# module_flags_calc.net
KiCad netlist of a schematic drawn in EAGLE
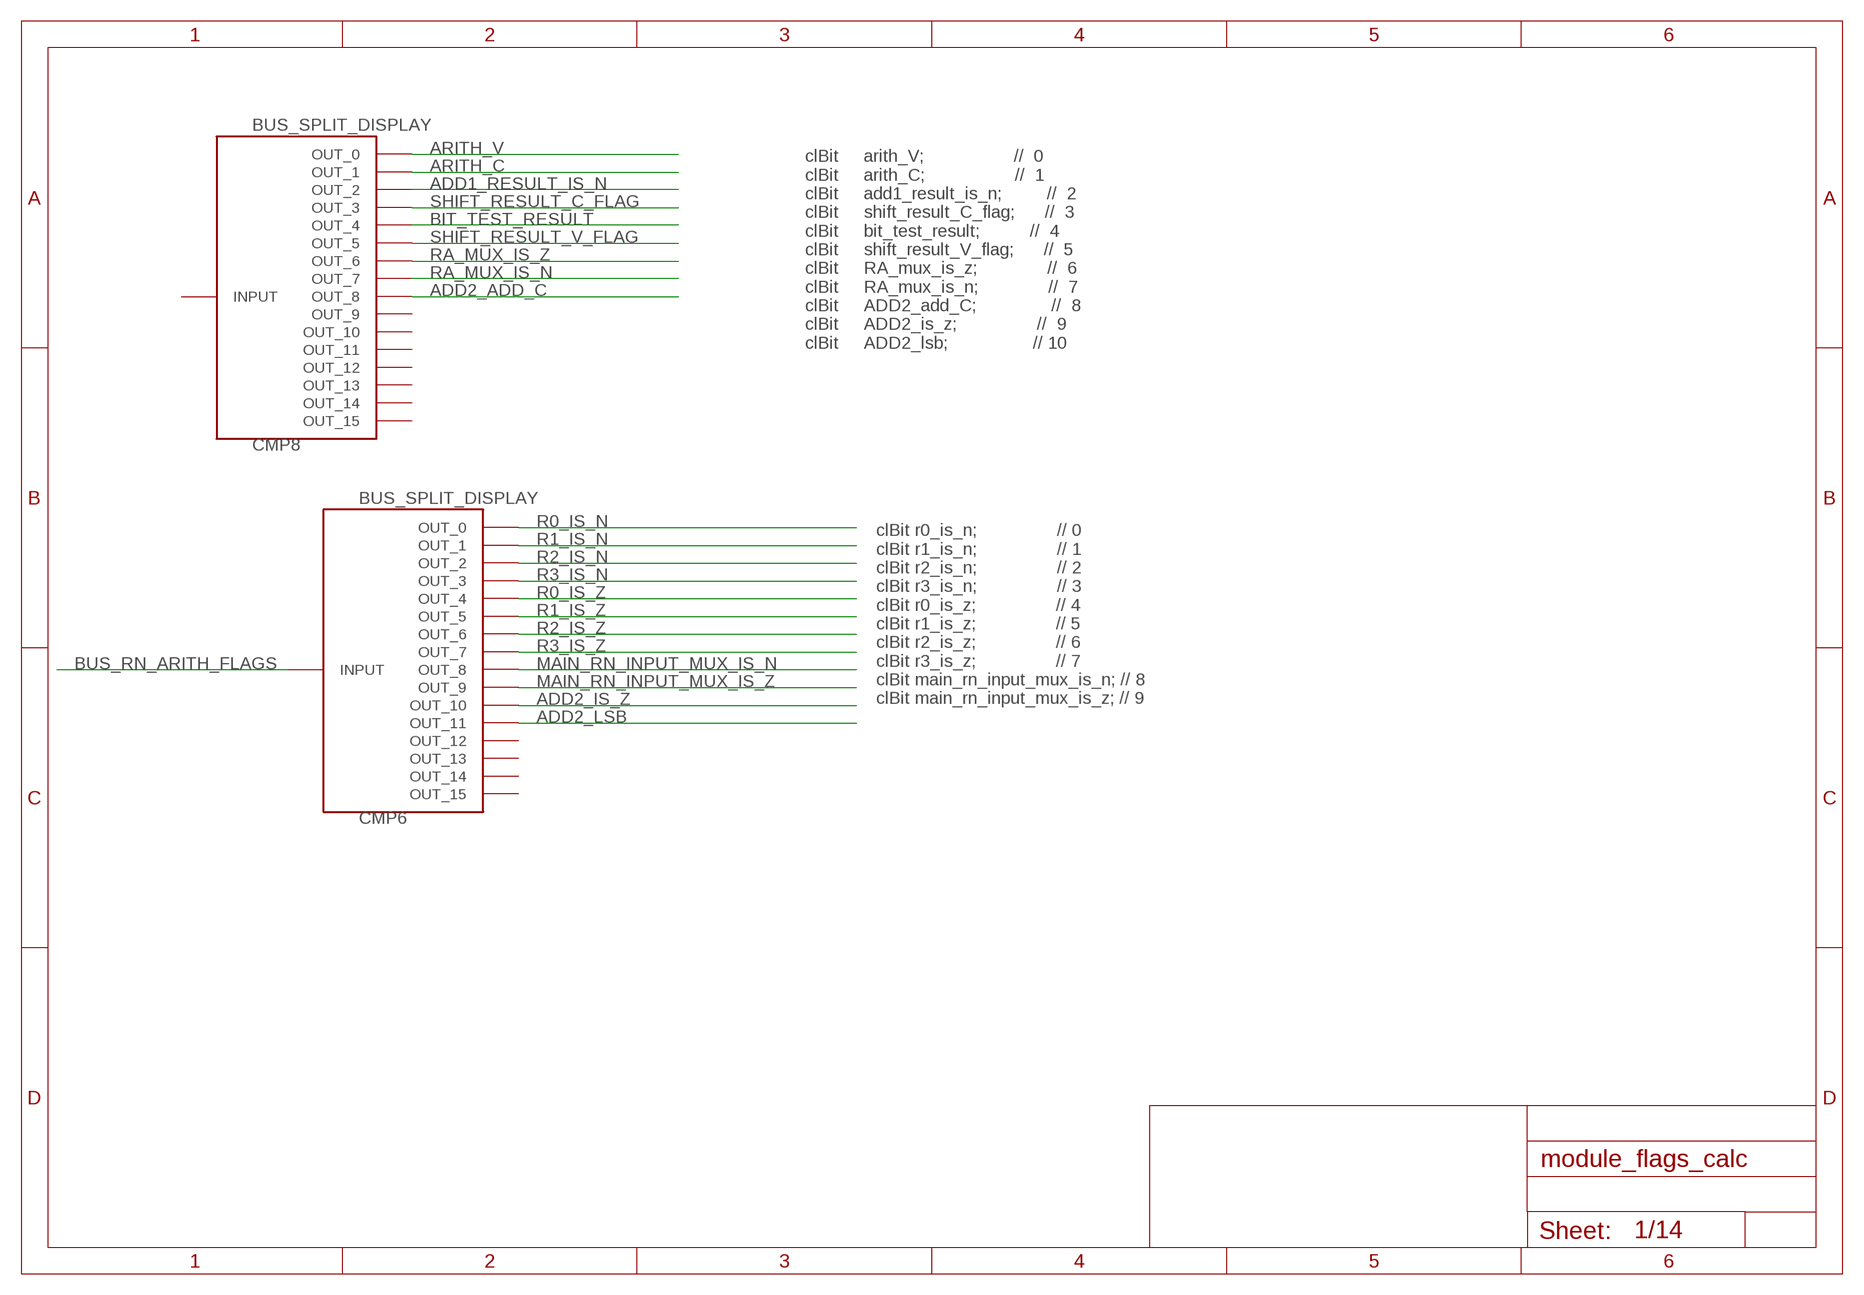
[diagram p0: schematic, sheet 1]
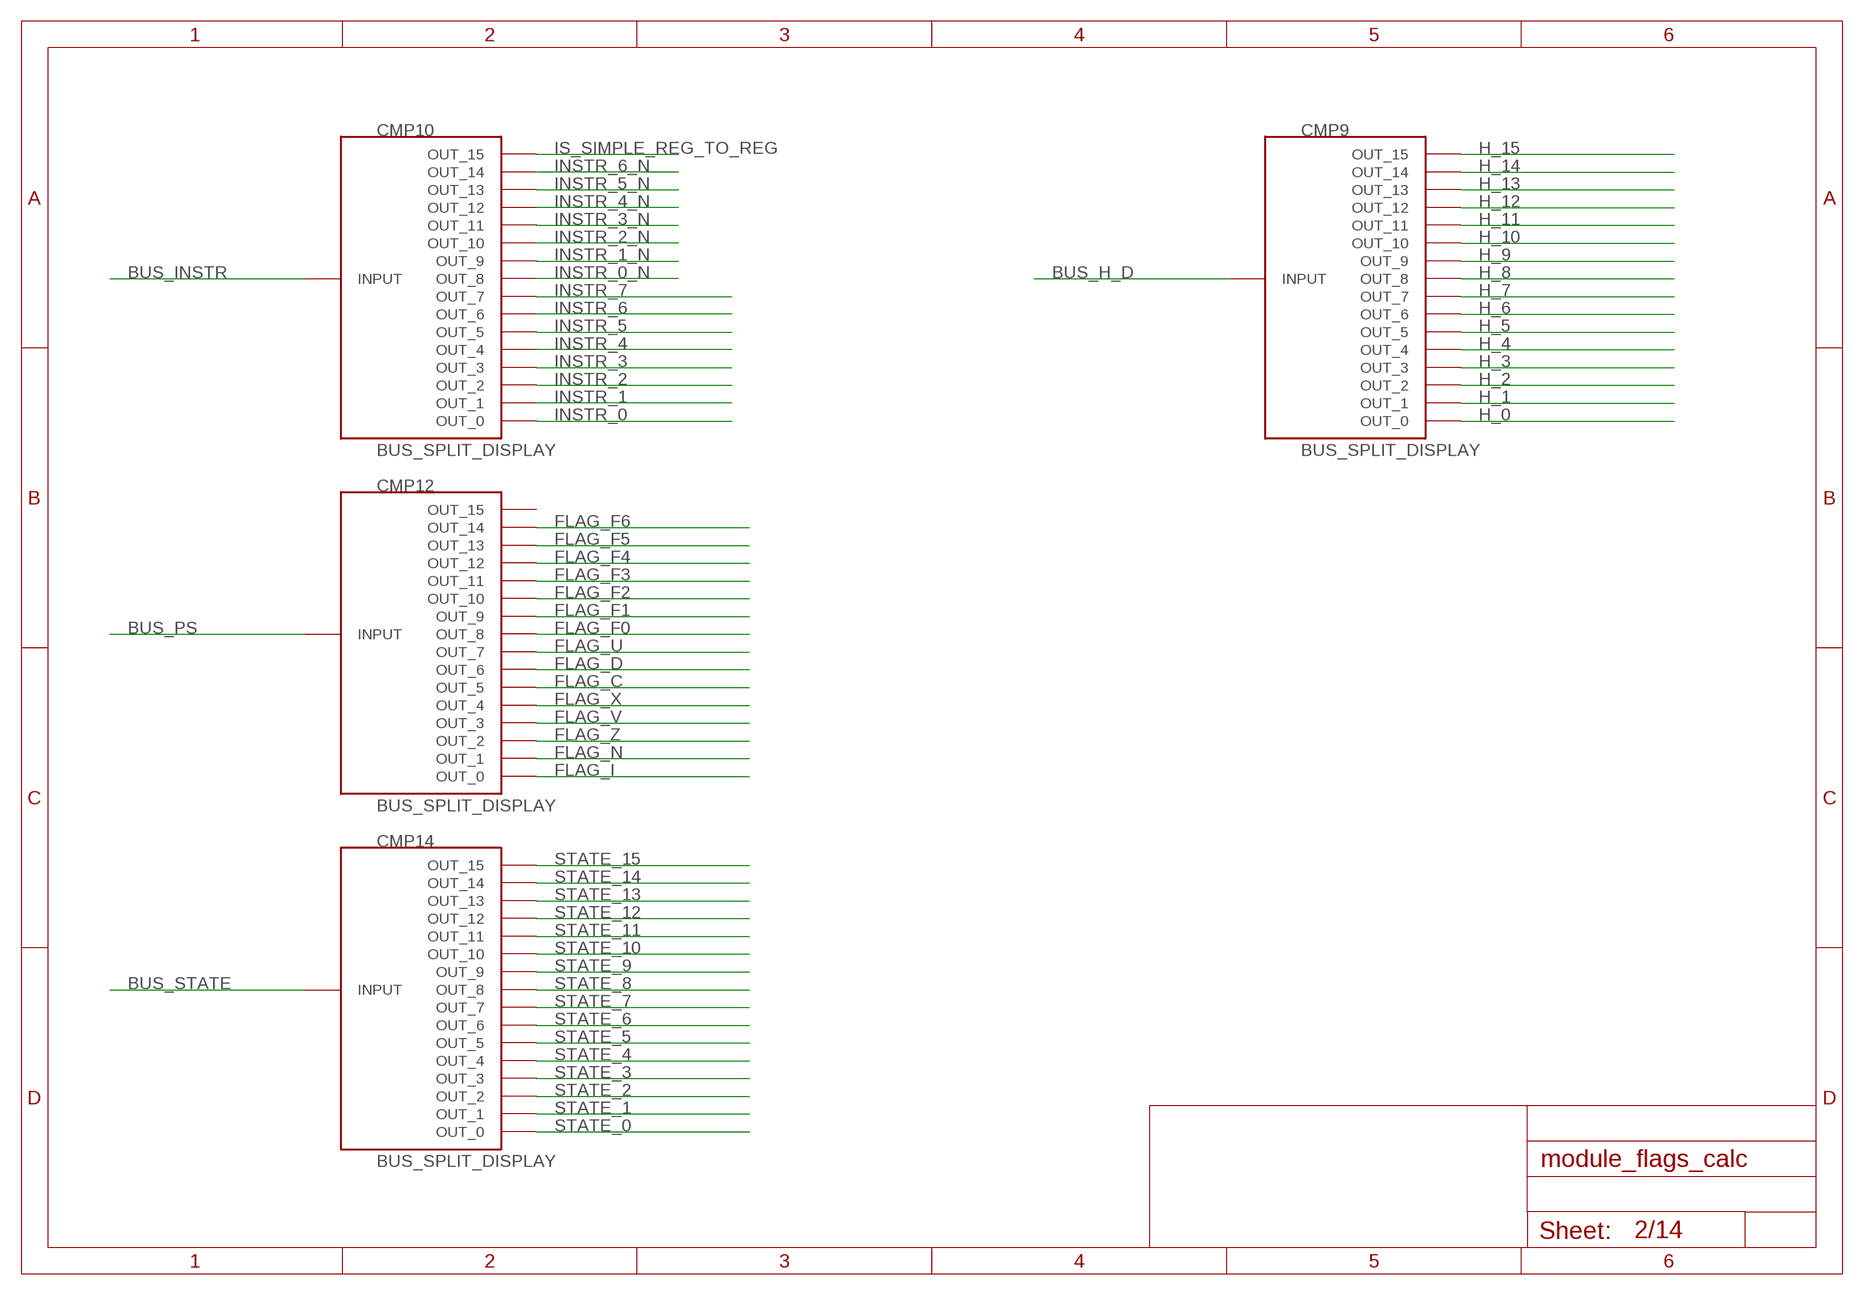
[diagram p1: schematic, sheet 2]
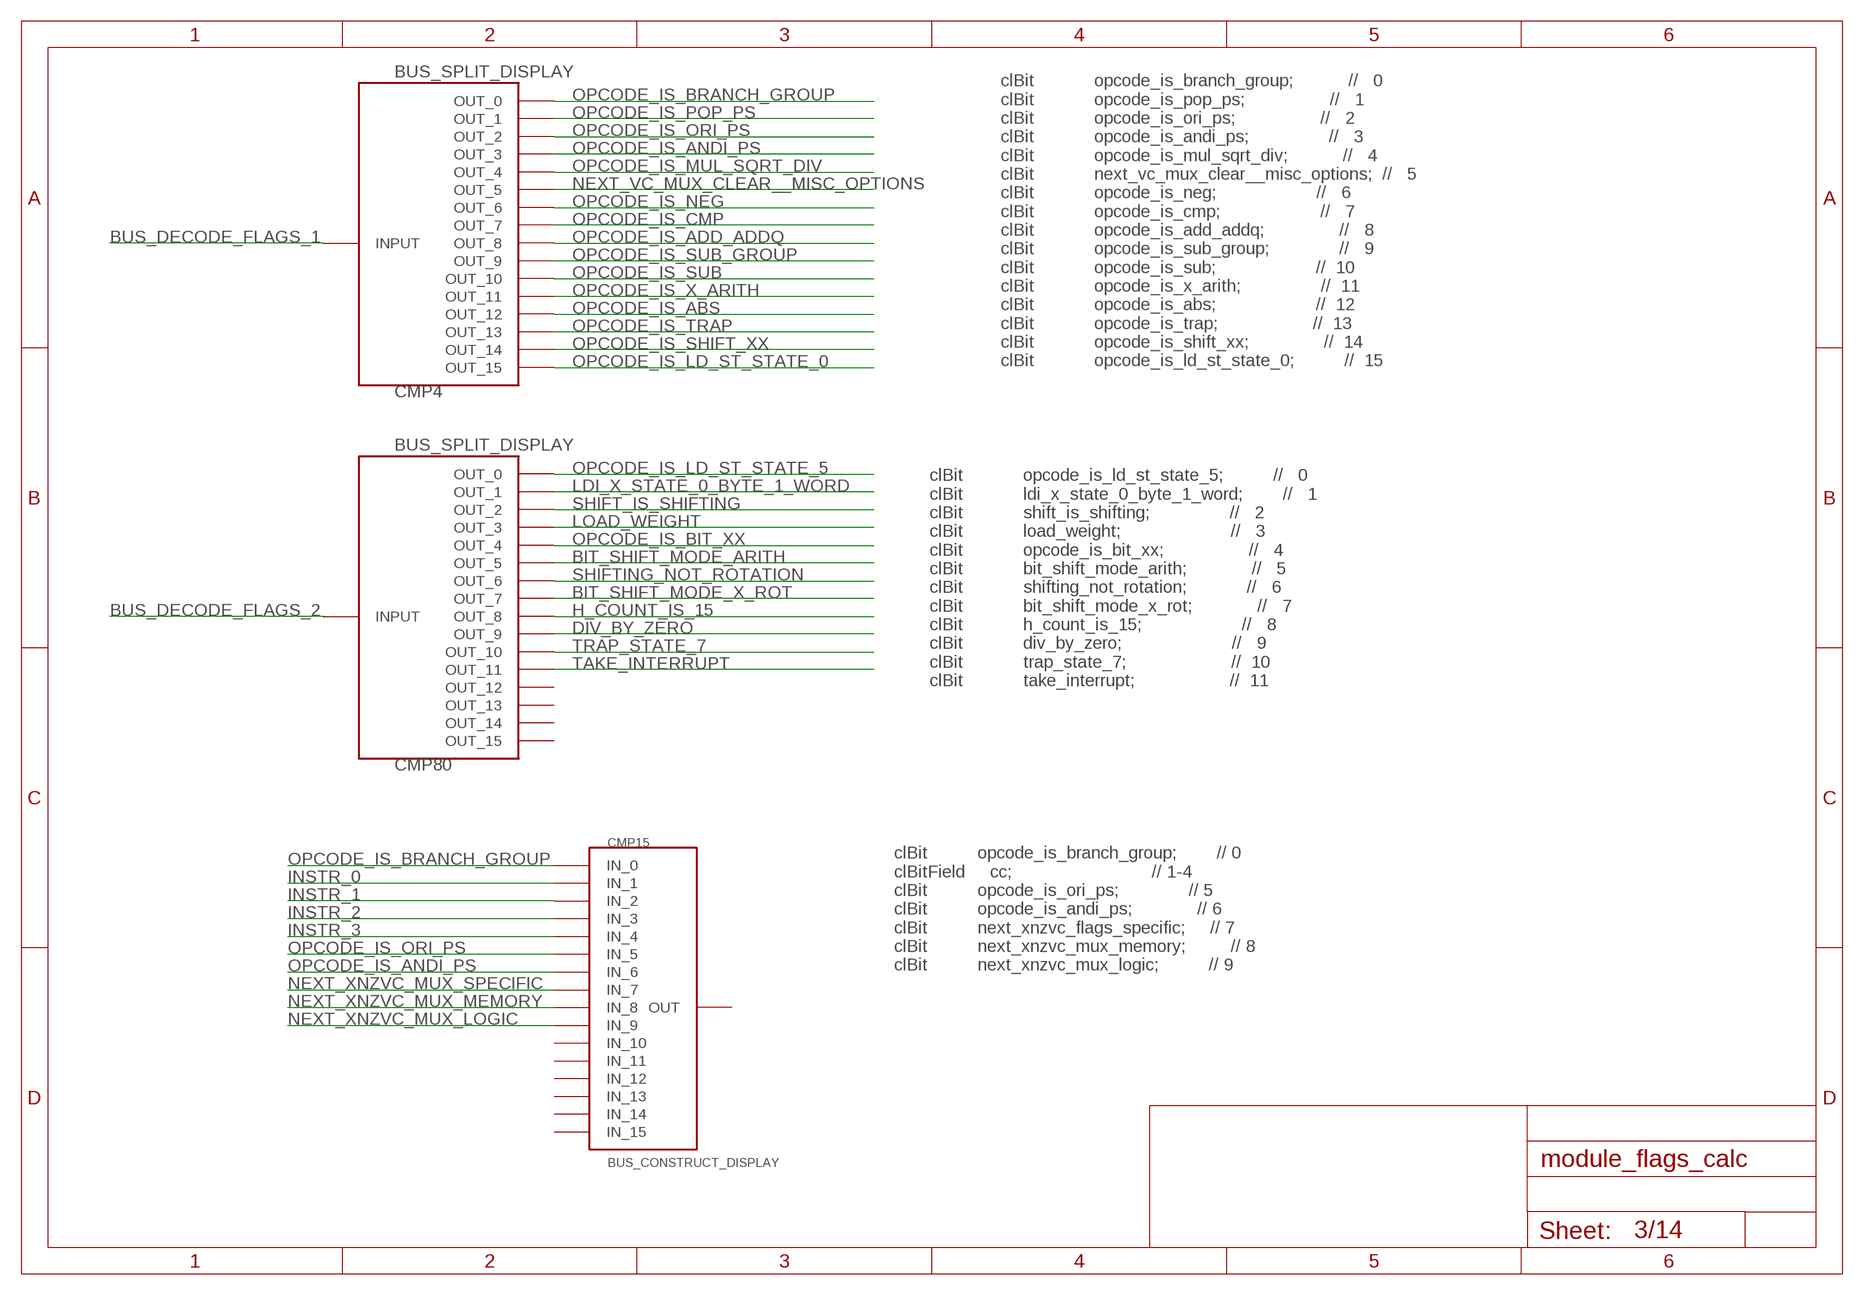
[diagram p2: schematic, sheet 3]
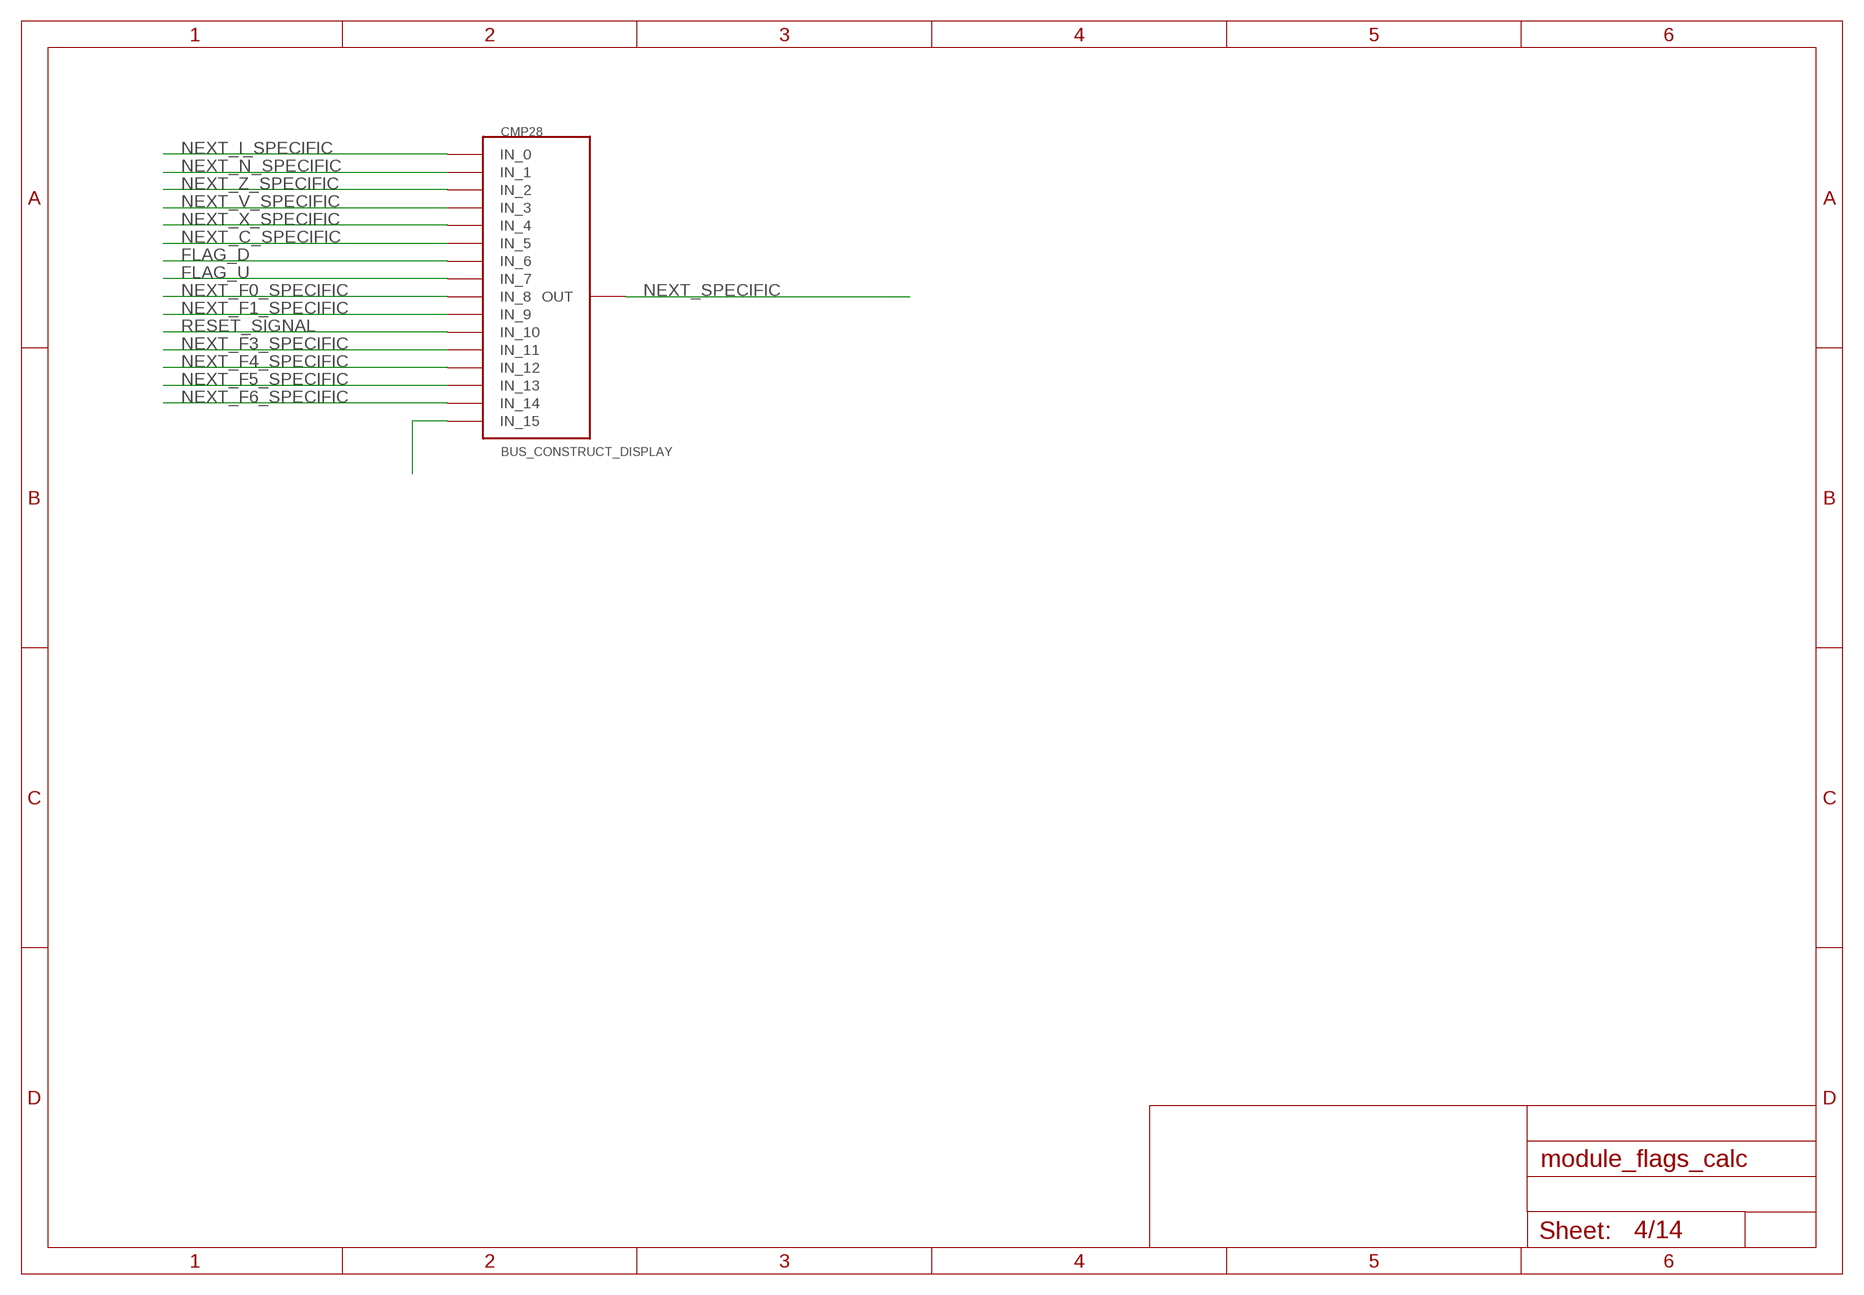
[diagram p3: schematic, sheet 4]
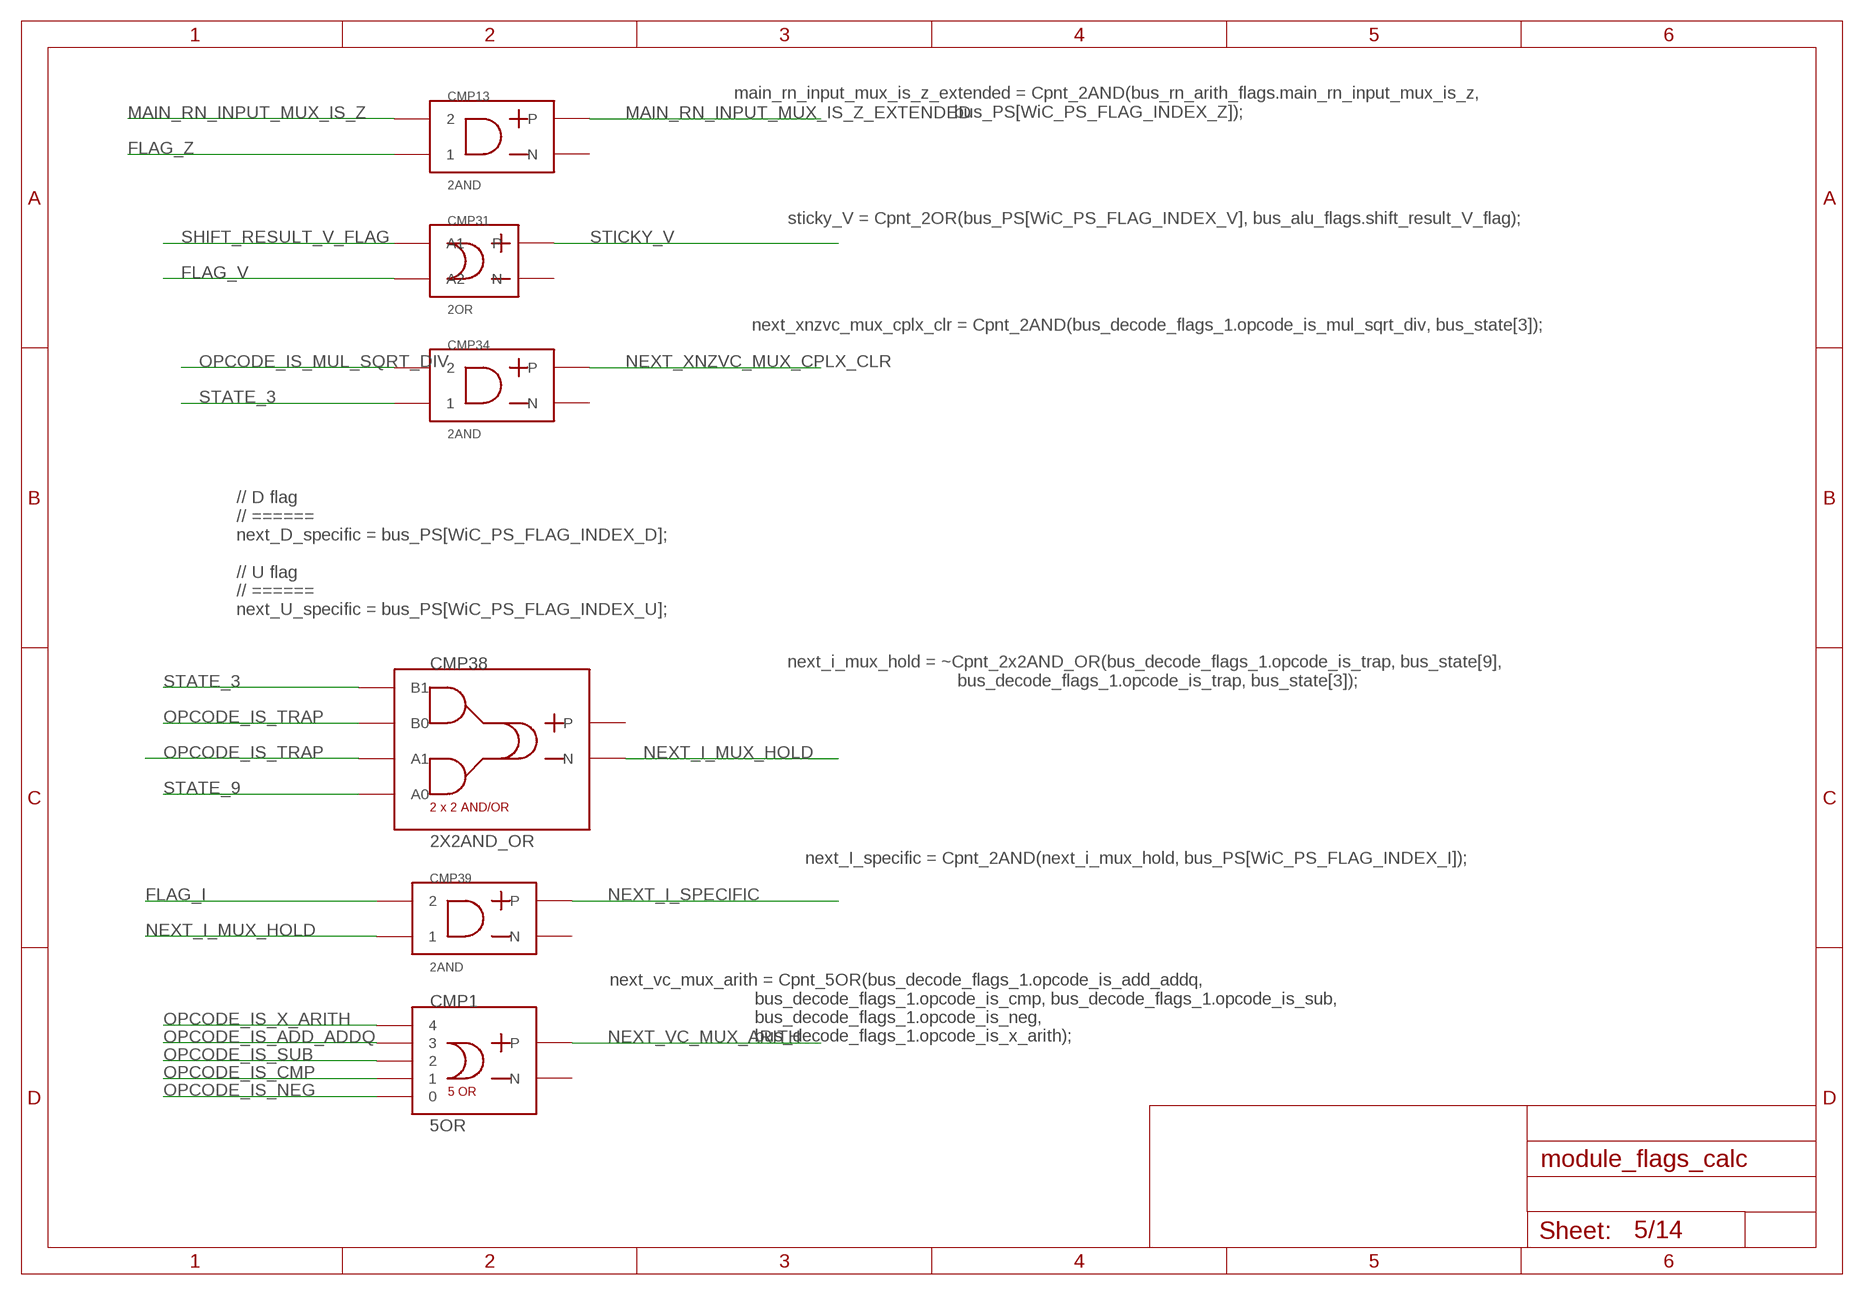
[diagram p4: schematic, sheet 5]
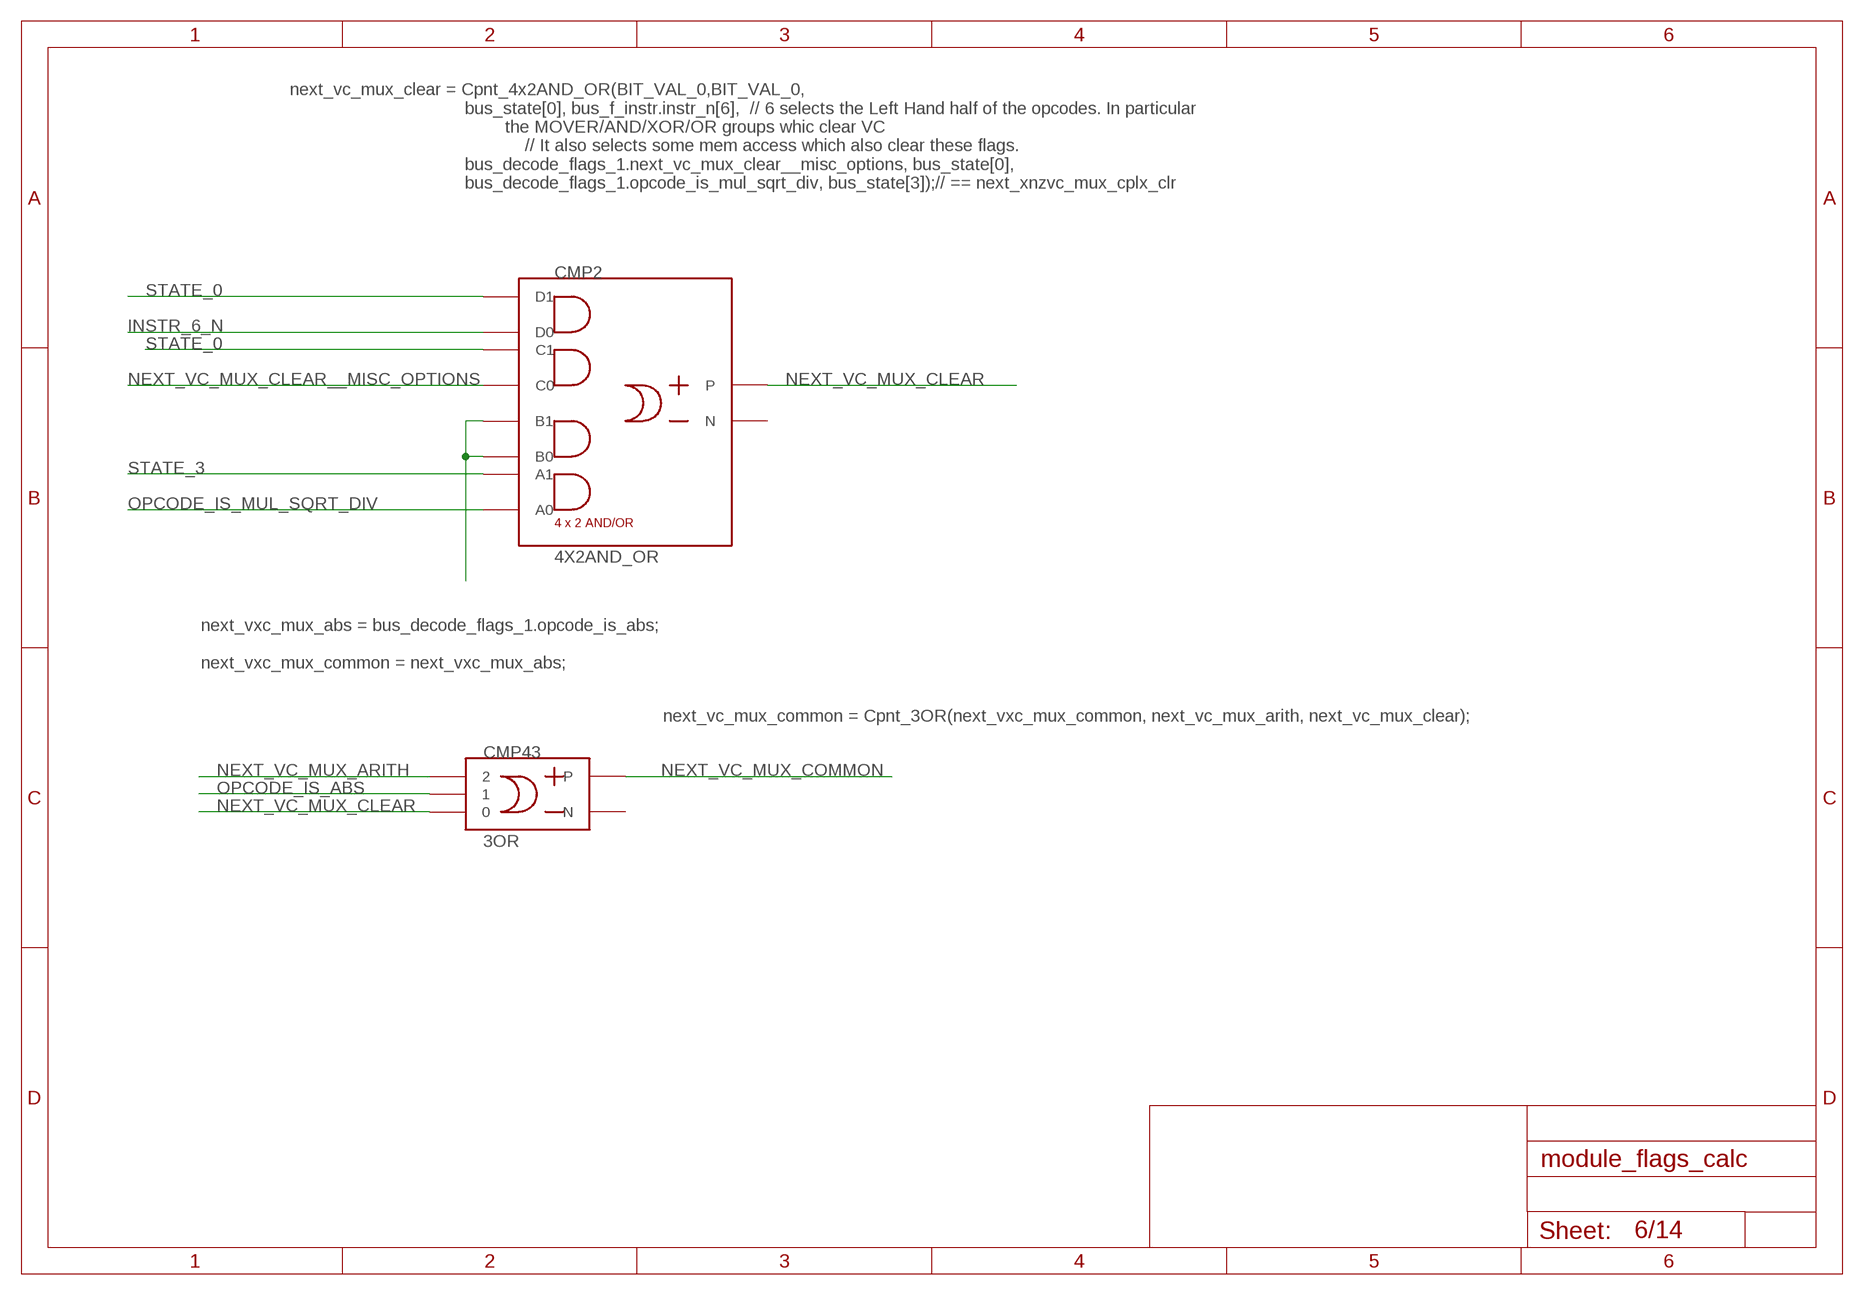
[diagram p5: schematic, sheet 6]
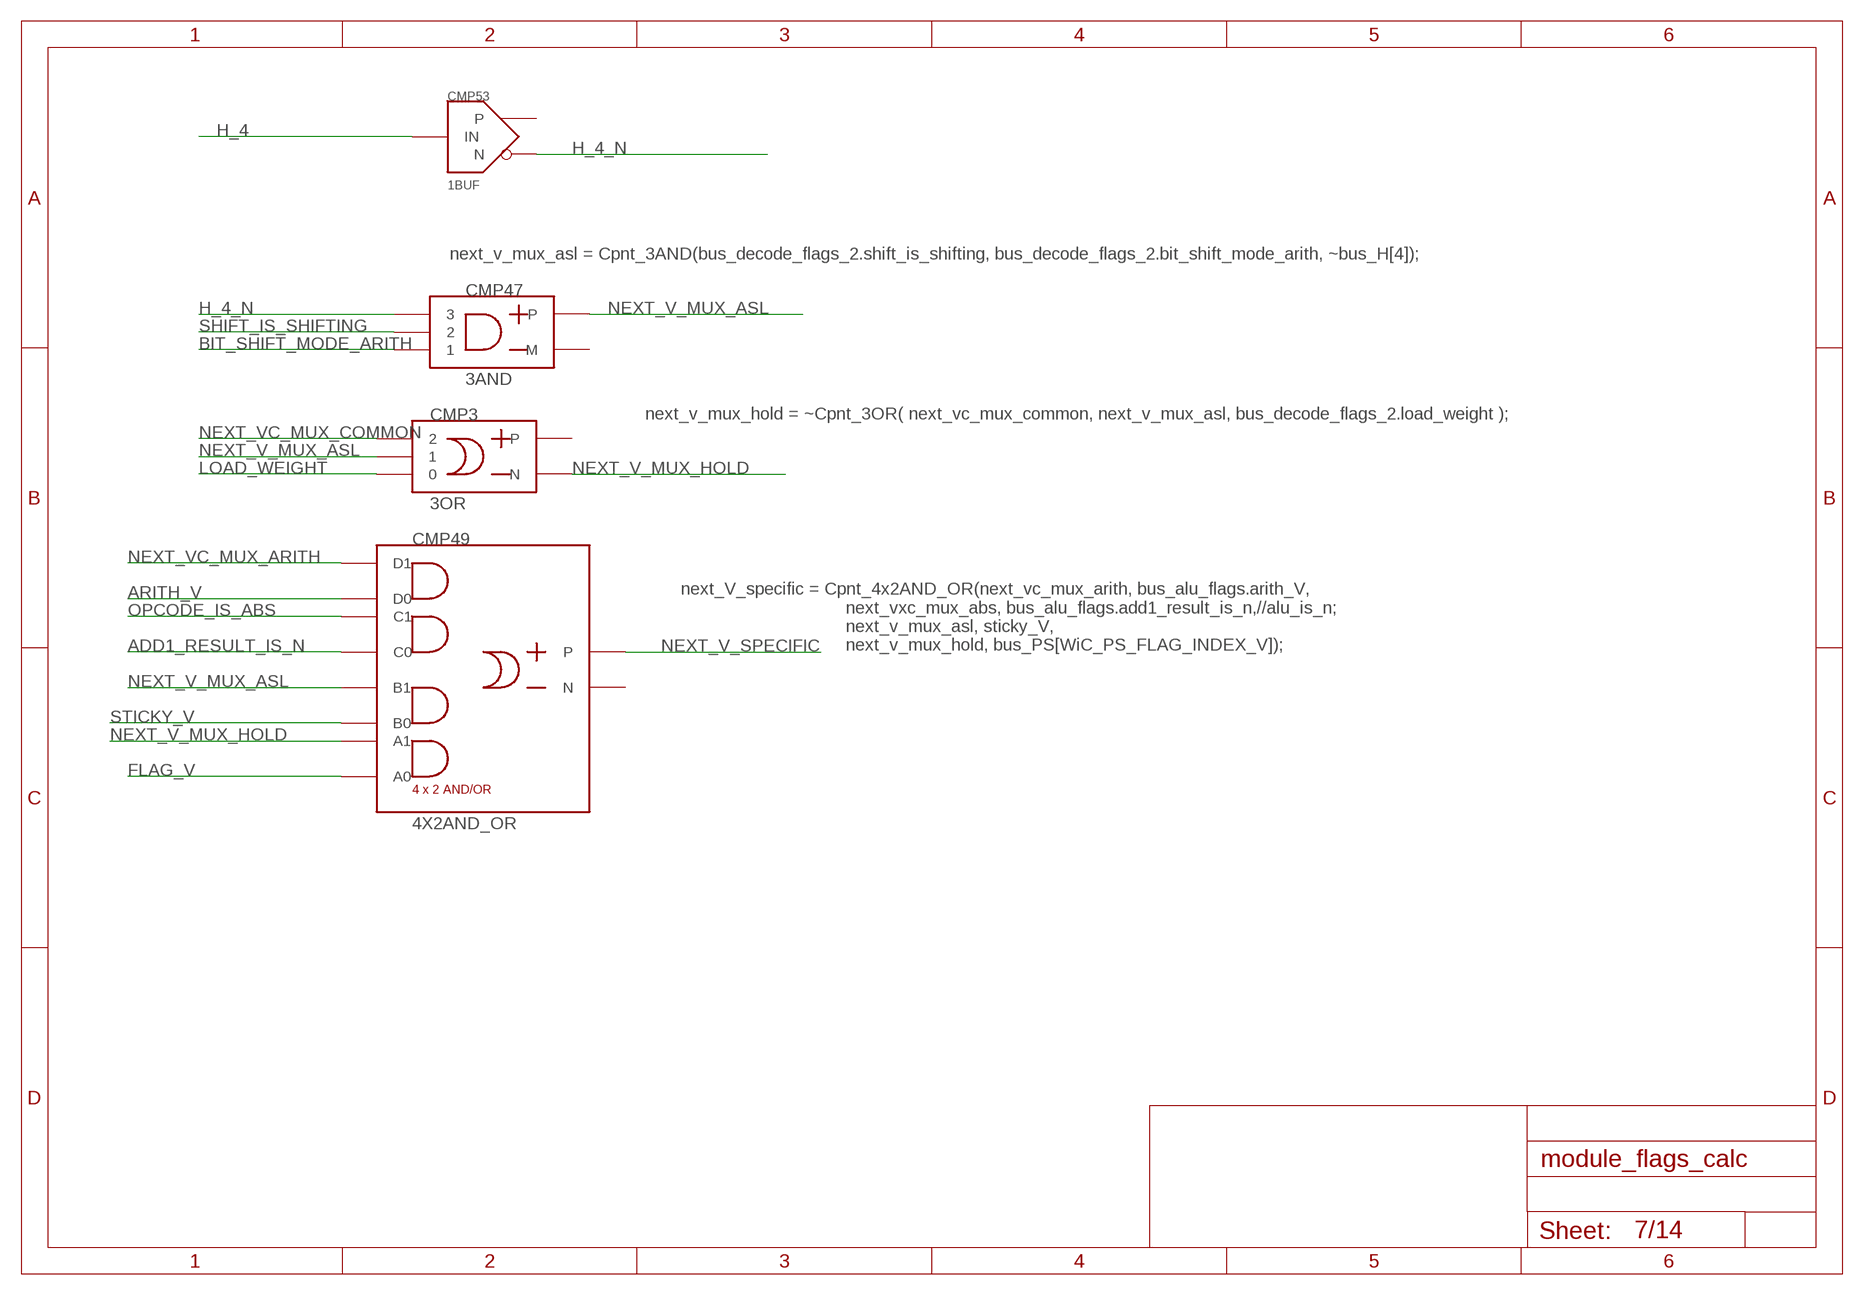
[diagram p6: schematic, sheet 7]
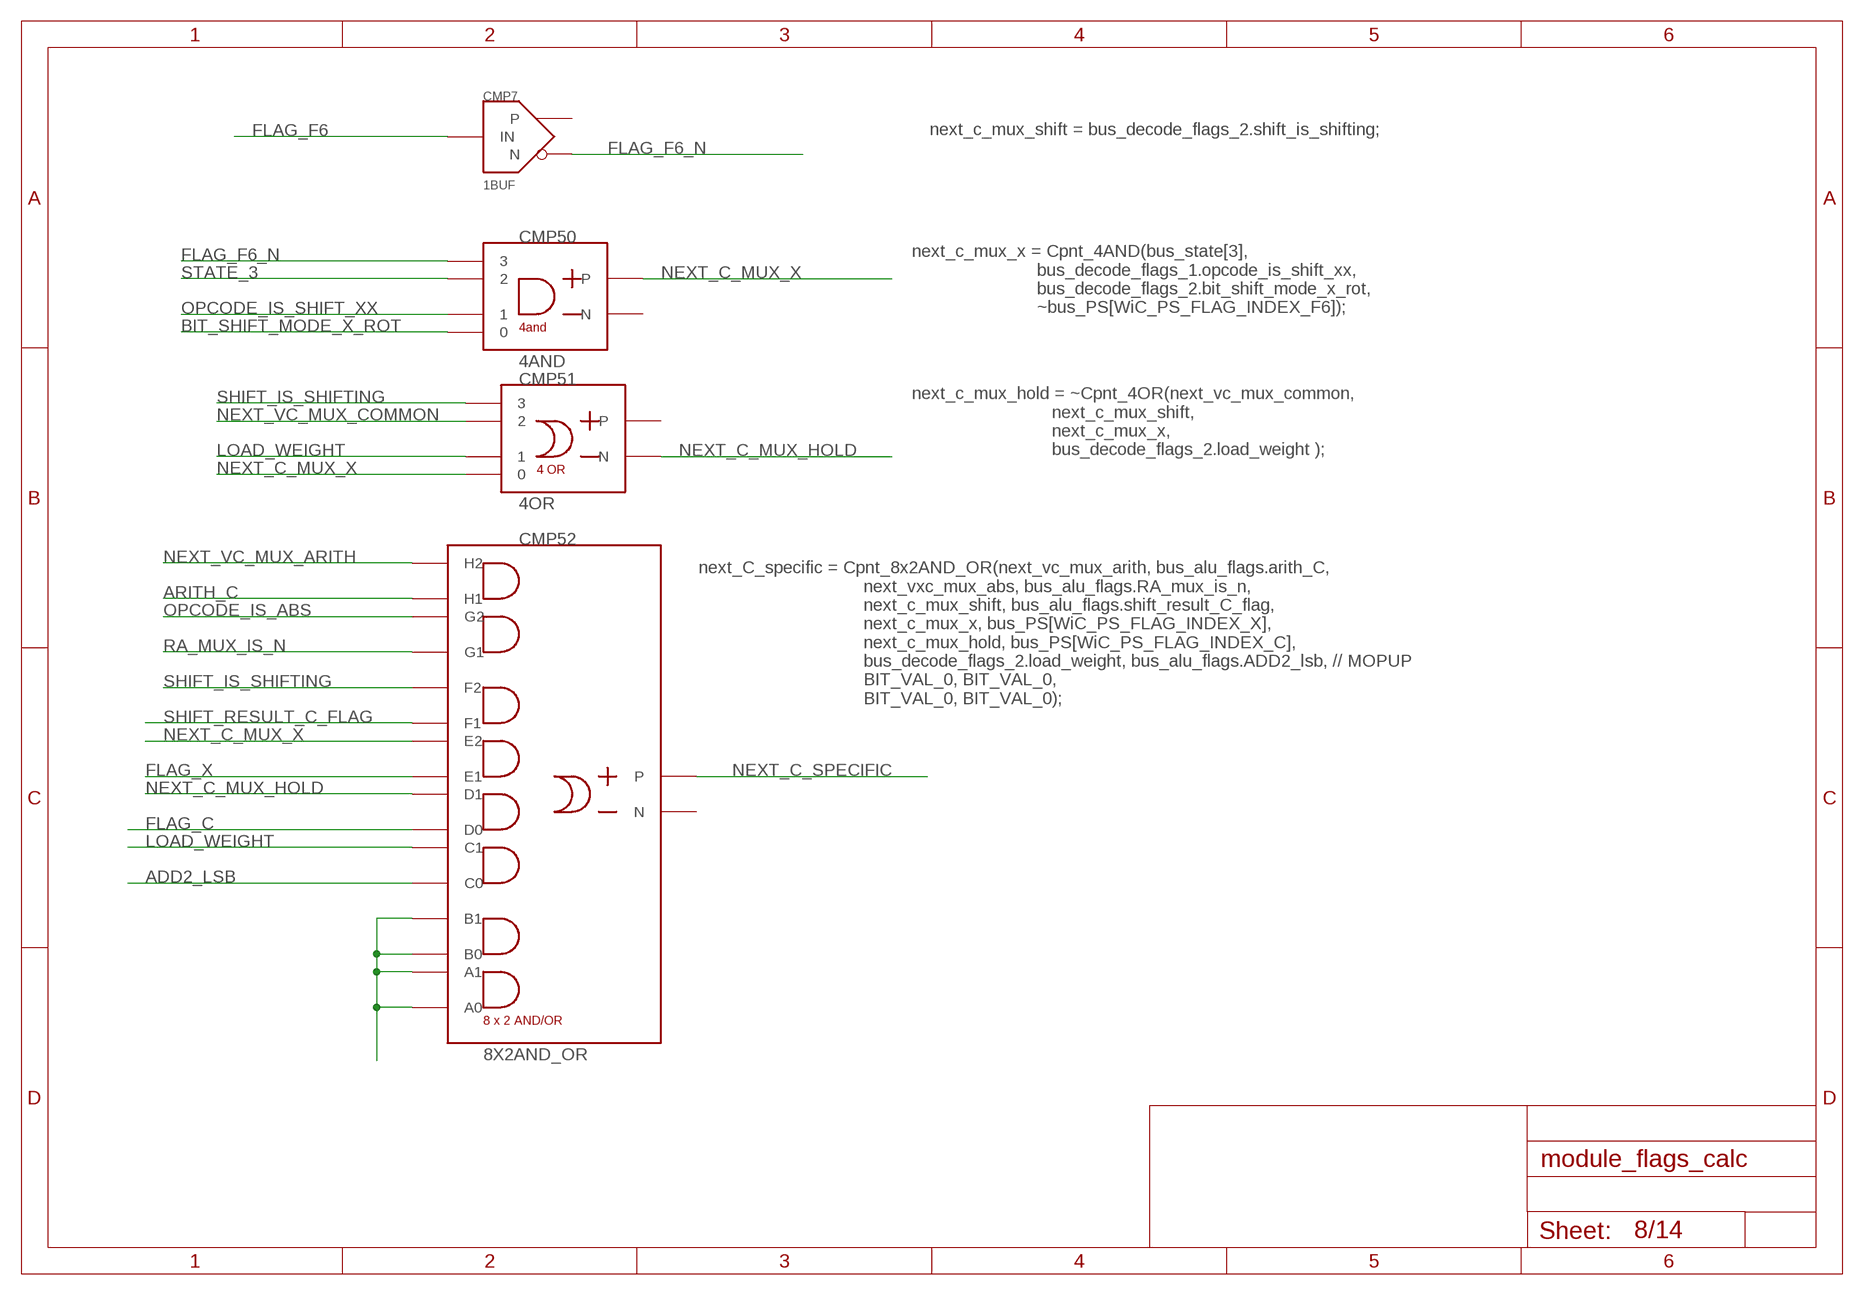
[diagram p7: schematic, sheet 8]
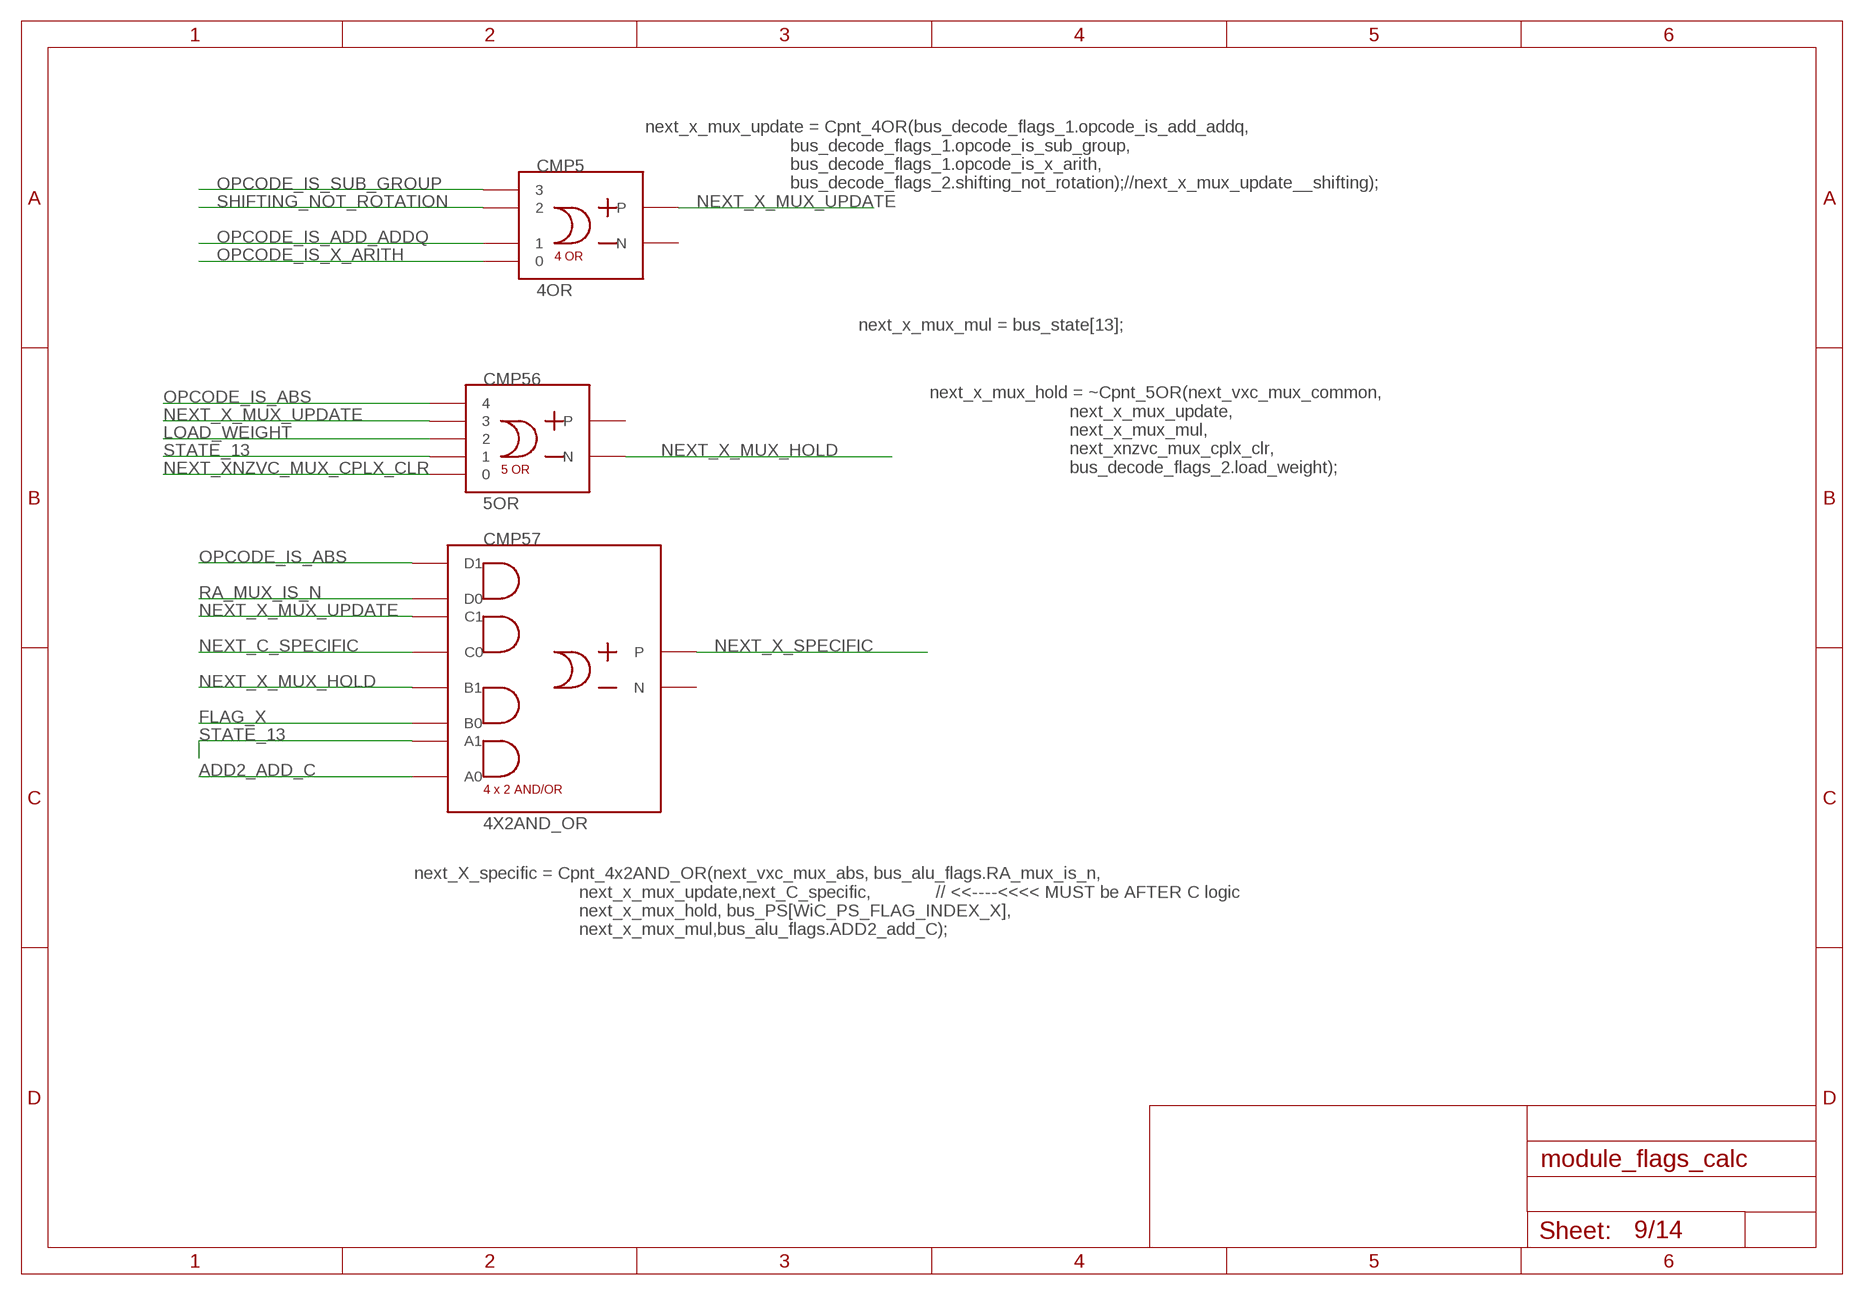
[diagram p8: schematic, sheet 9]
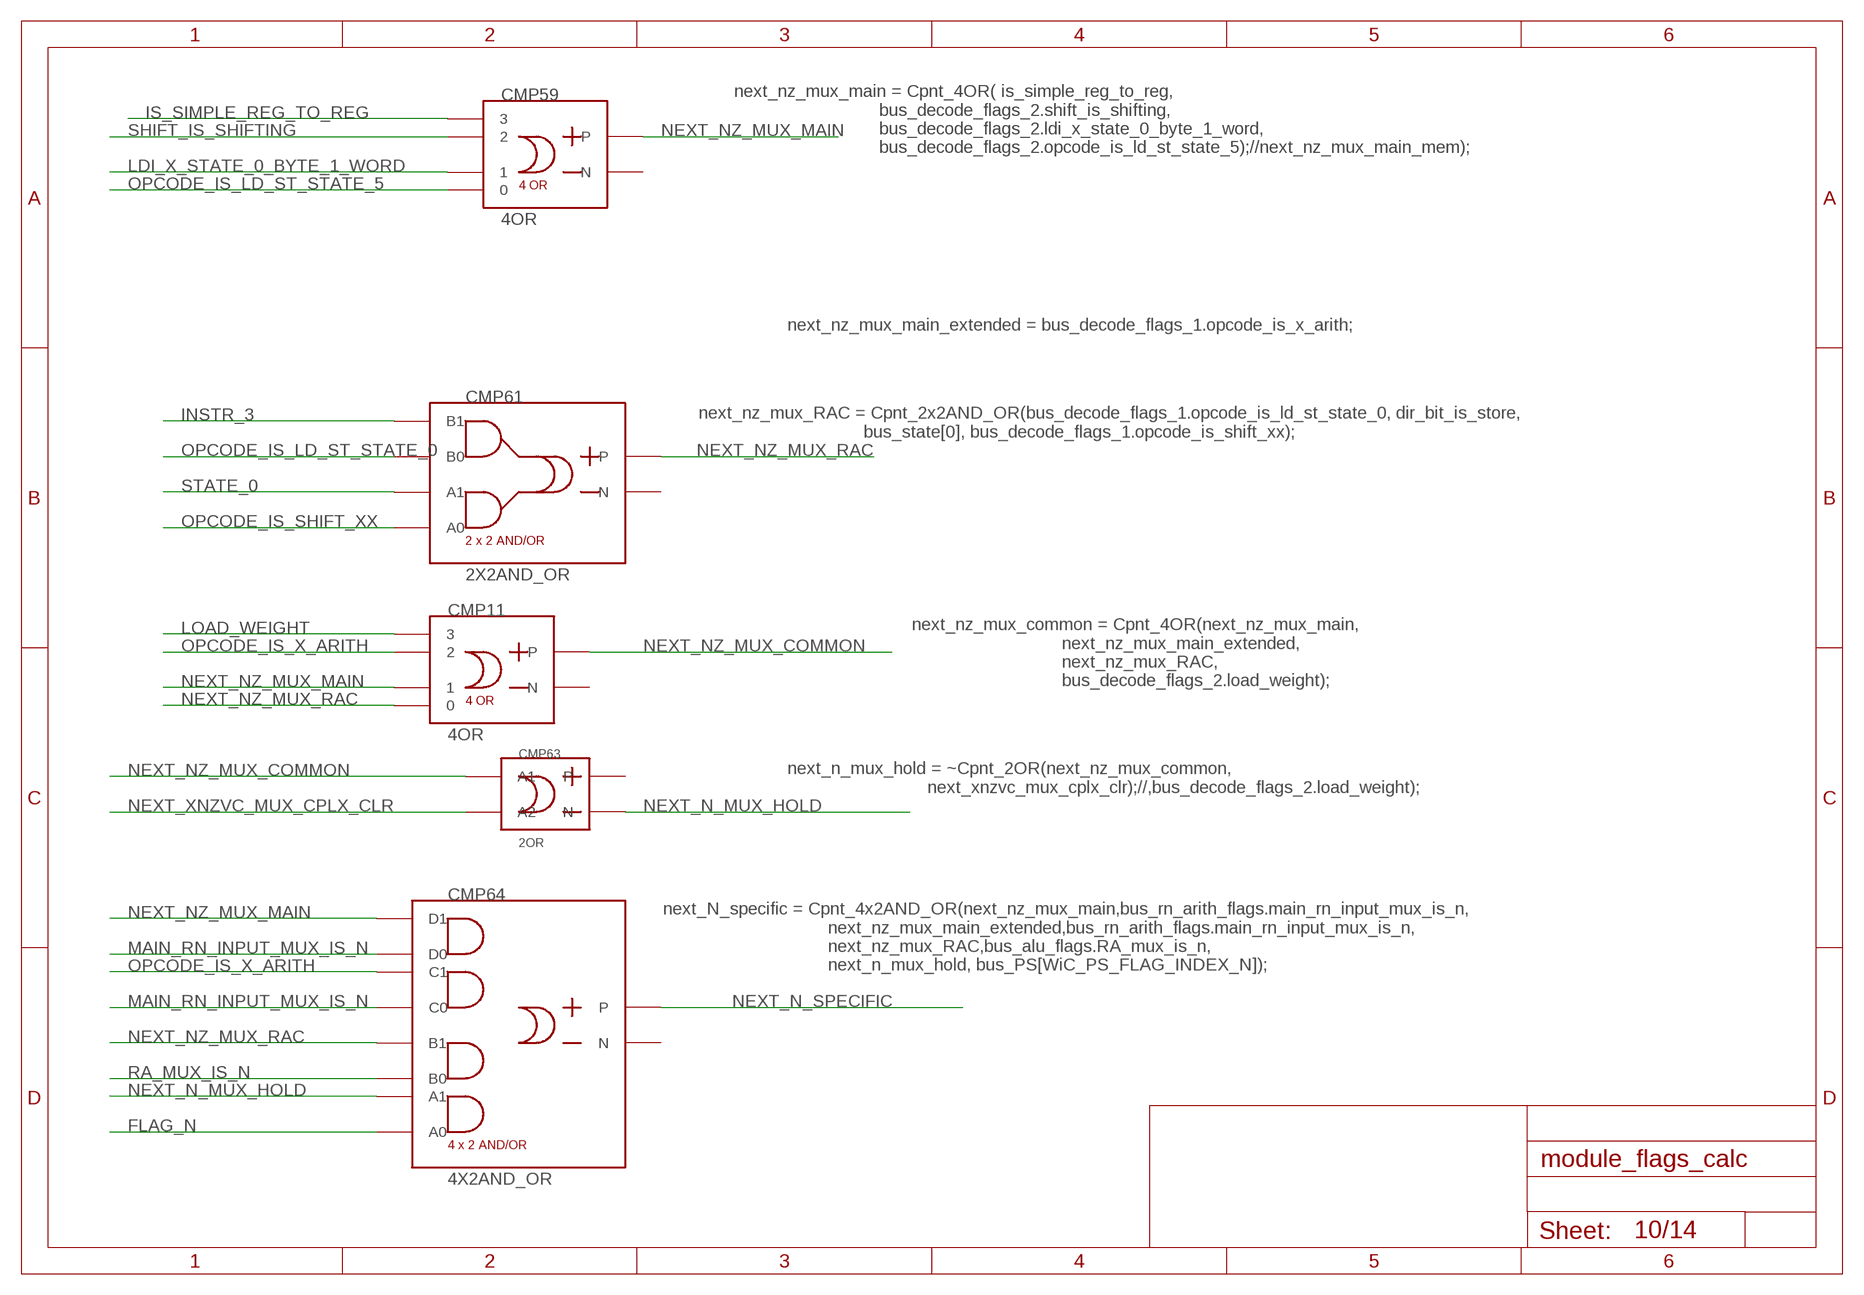
[diagram p9: schematic, sheet 10]
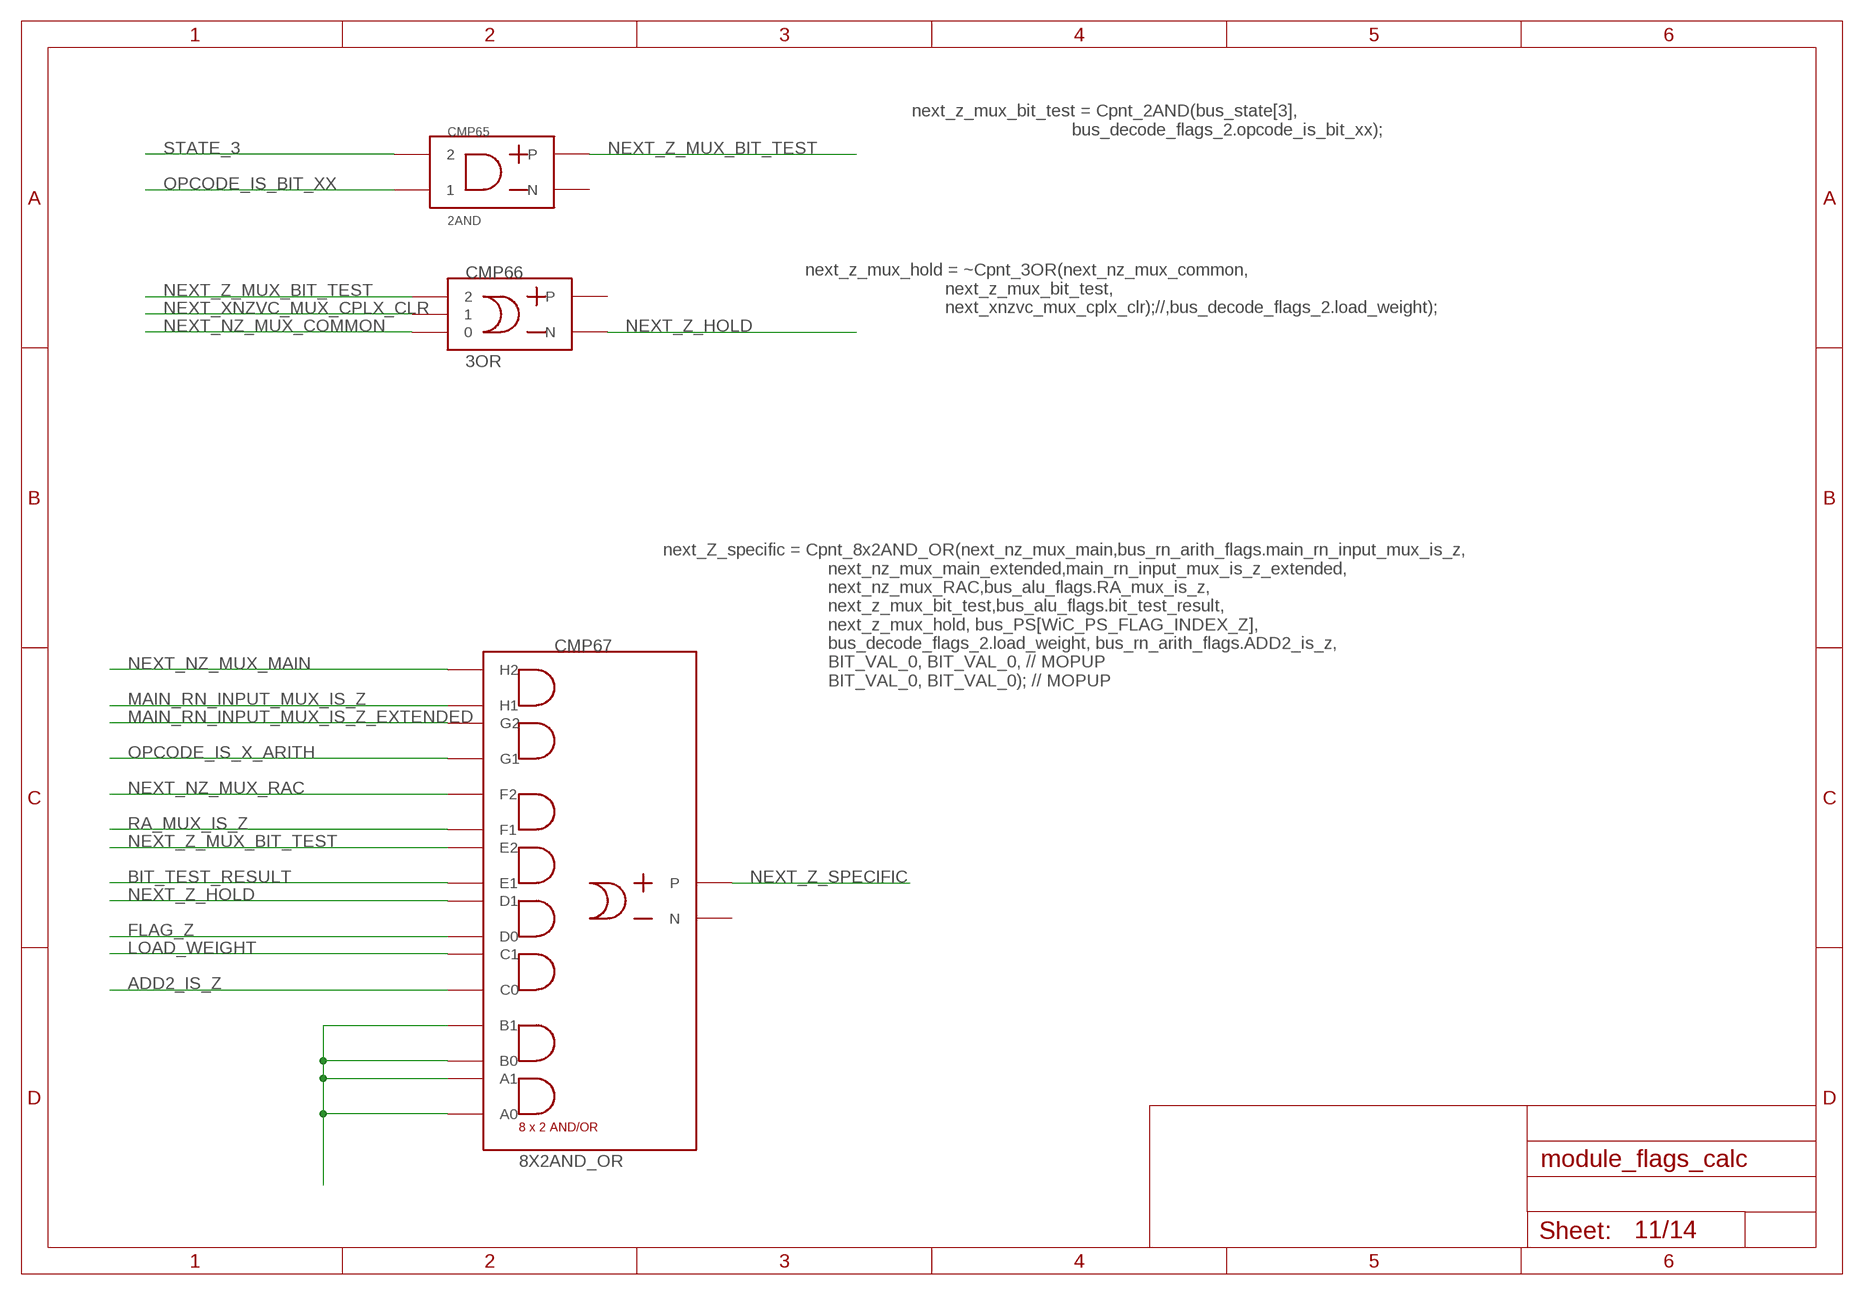
[diagram p10: schematic, sheet 11]
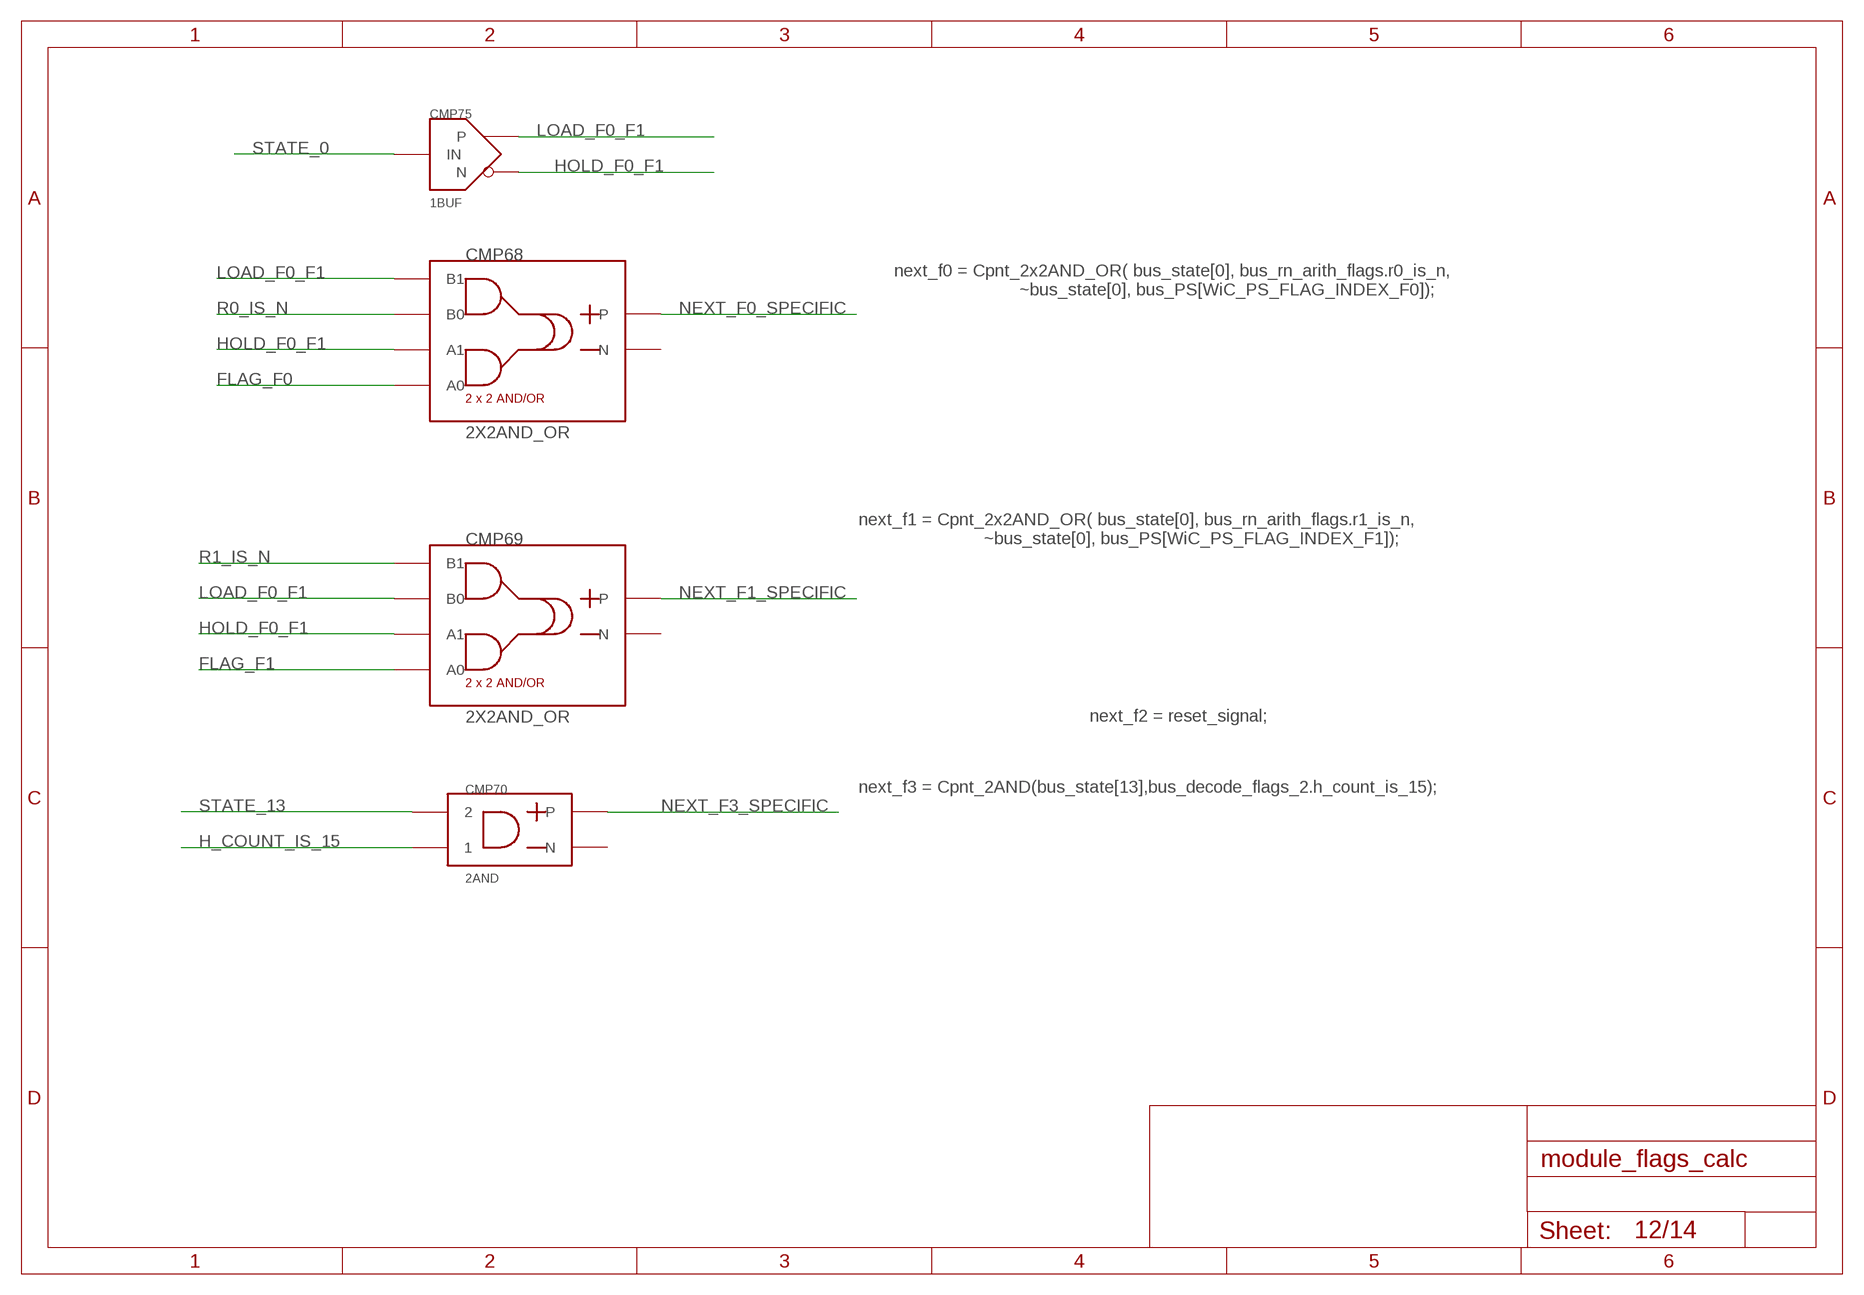
[diagram p11: schematic, sheet 12]
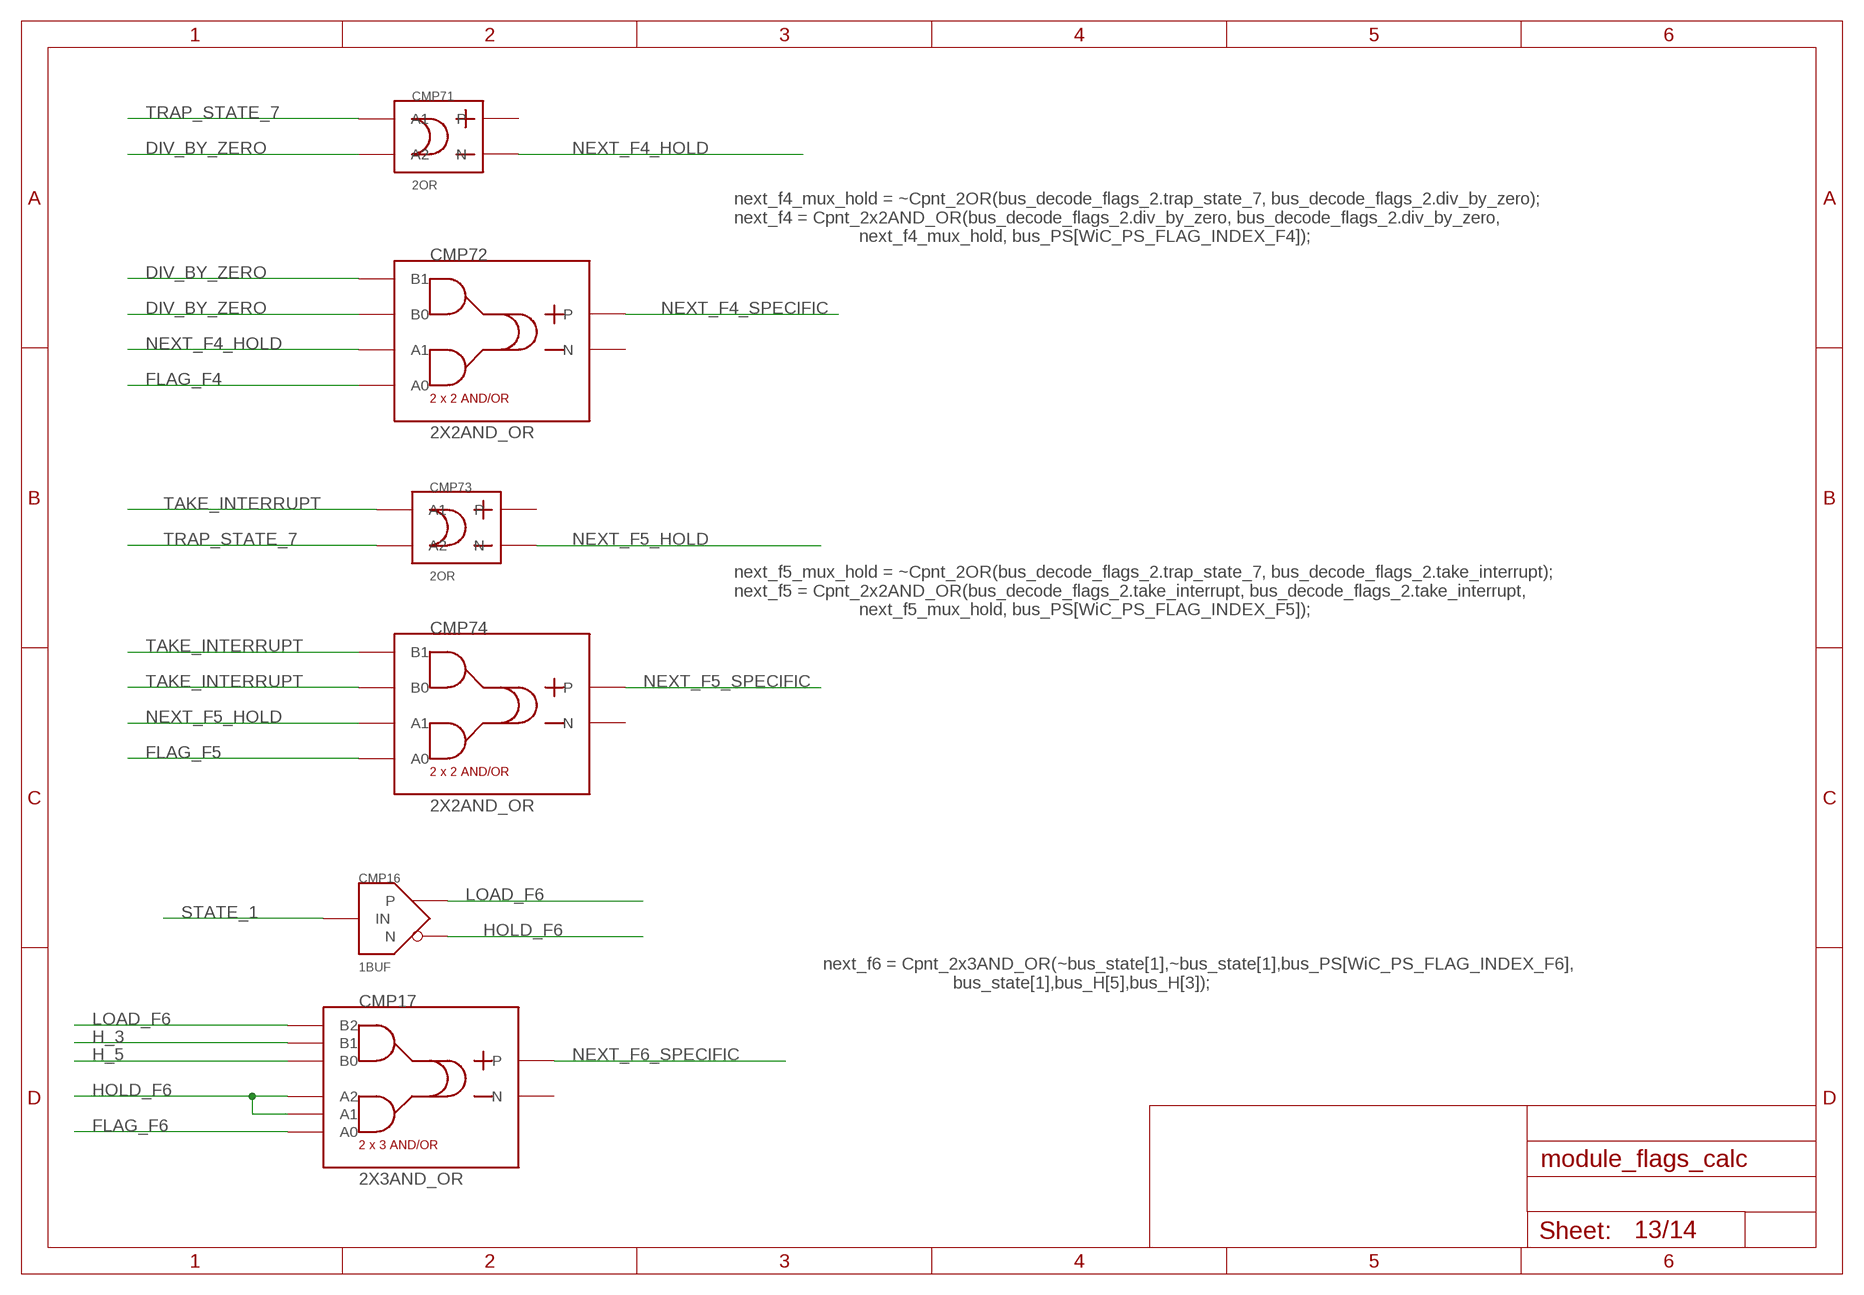
[diagram p12: schematic, sheet 13]
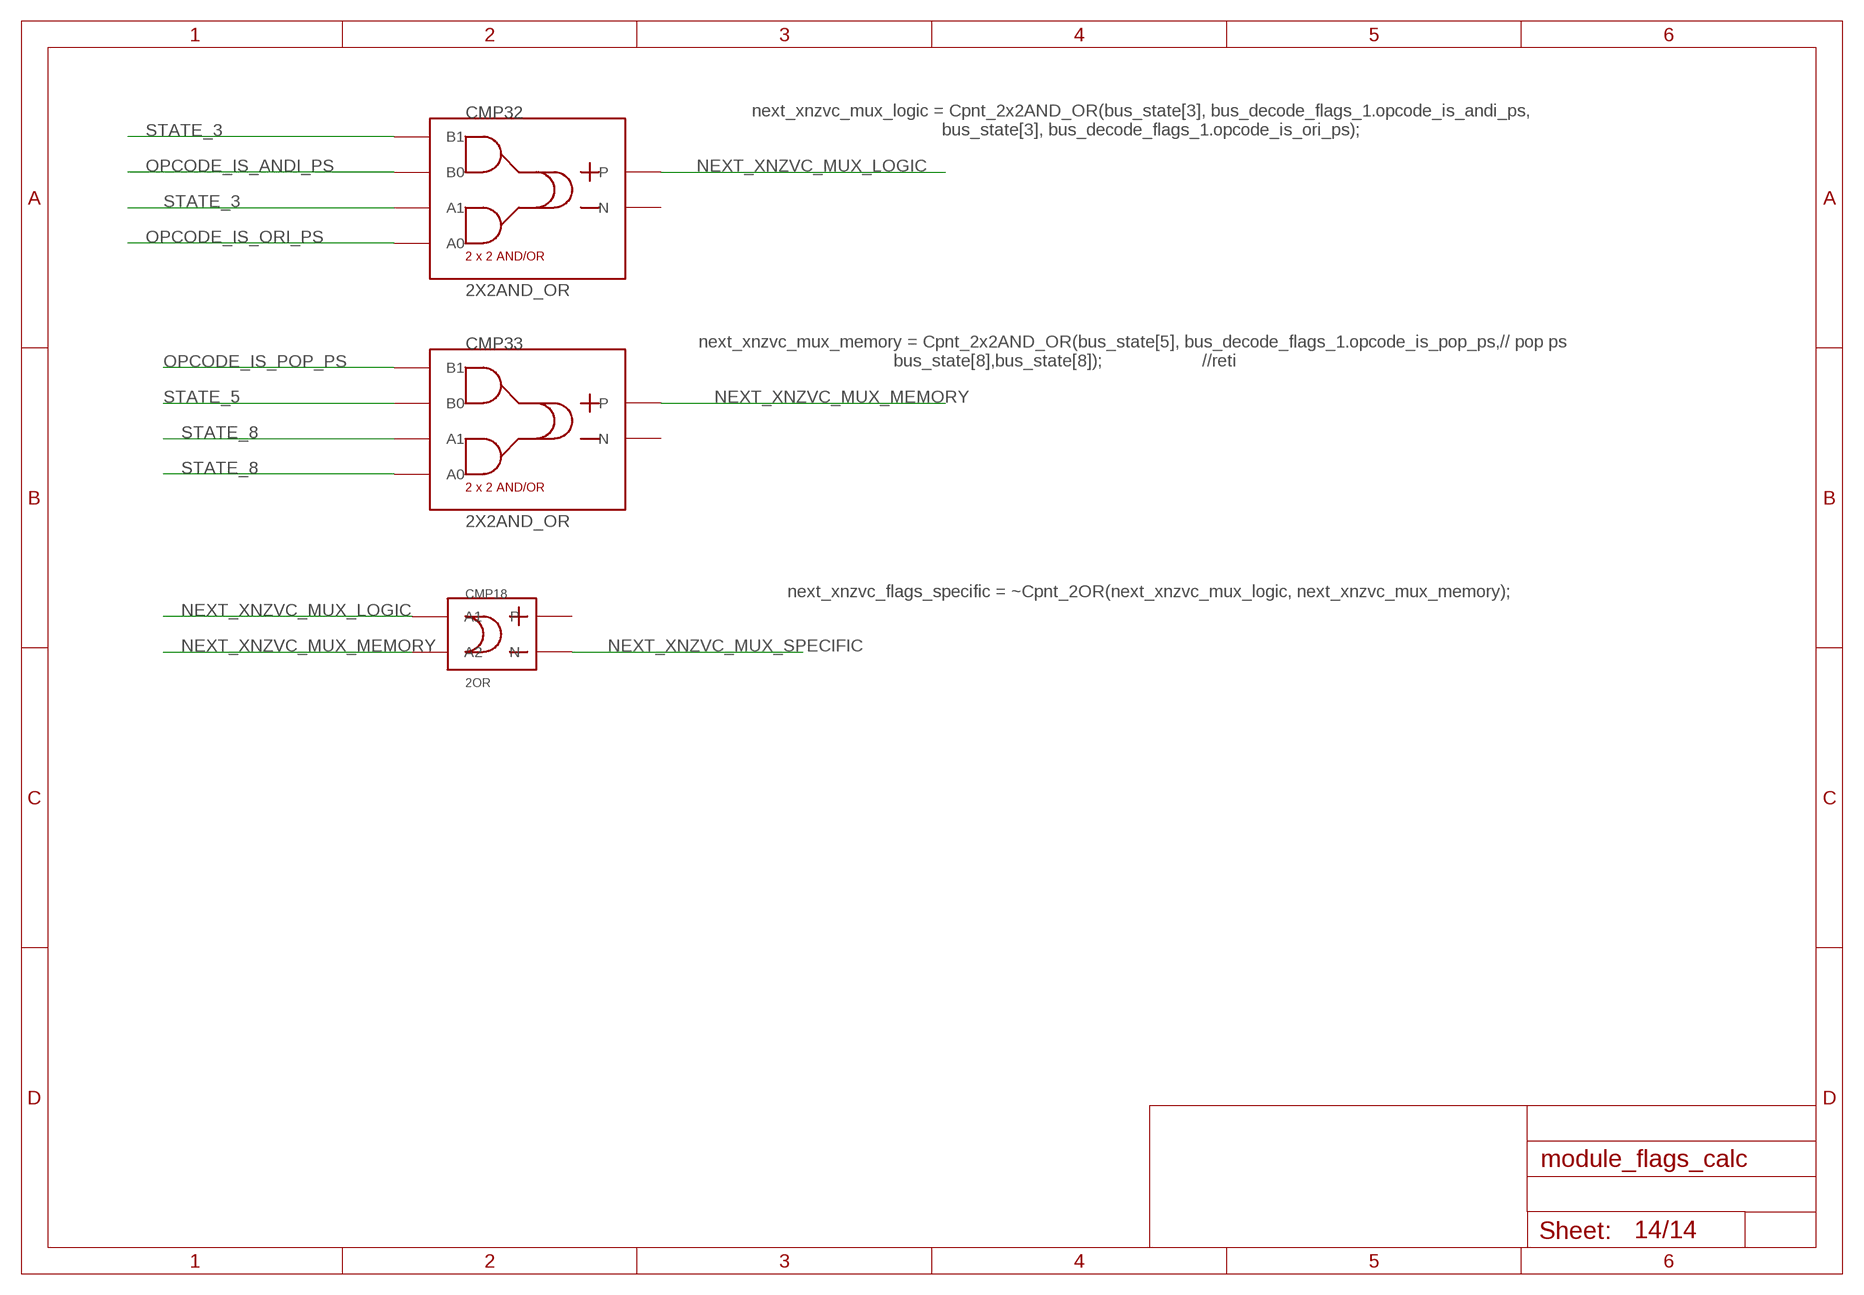
[diagram p13: schematic, sheet 14]

(export (version "E")
  (design (tool "Eeschema 10.0.6"))
  (components
    (comp (ref "CMP6")
      (value "BUS_SPLIT_DISPLAY")
      (footprint "eagle-import:BUS_SPLIT_DISPLAY")
      (libsource (lib "eagle-import") (part "BUS_SPLIT_DISPLAY"))
    )
    (comp (ref "CMP8")
      (value "BUS_SPLIT_DISPLAY")
      (footprint "eagle-import:BUS_SPLIT_DISPLAY")
      (libsource (lib "eagle-import") (part "BUS_SPLIT_DISPLAY"))
    )
    (comp (ref "CMP7")
      (value "1BUF")
      (footprint "eagle-import:1BUF")
      (libsource (lib "eagle-import") (part "1BUF"))
    )
    (comp (ref "CMP50")
      (value "4AND")
      (footprint "eagle-import:4AND")
      (libsource (lib "eagle-import") (part "4AND"))
    )
    (comp (ref "CMP51")
      (value "4OR")
      (footprint "eagle-import:4OR")
      (libsource (lib "eagle-import") (part "4OR"))
    )
    (comp (ref "CMP52")
      (value "8X2AND_OR")
      (footprint "eagle-import:8X2AND_OR")
      (libsource (lib "eagle-import") (part "8X2AND_OR"))
    )
    (comp (ref "CMP28")
      (value "BUS_CONSTRUCT_DISPLAY")
      (footprint "eagle-import:BUS_SPLIT_DISPLAY")
      (libsource (lib "eagle-import") (part "BUS_CONSTRUCT_DISPLAY"))
    )
    (comp (ref "CMP16")
      (value "1BUF")
      (footprint "eagle-import:1BUF")
      (libsource (lib "eagle-import") (part "1BUF"))
    )
    (comp (ref "CMP17")
      (value "2X3AND_OR")
      (footprint "eagle-import:2X3AND_OR")
      (libsource (lib "eagle-import") (part "2X3AND_OR"))
    )
    (comp (ref "CMP71")
      (value "2OR")
      (footprint "eagle-import:2OR")
      (libsource (lib "eagle-import") (part "2OR"))
    )
    (comp (ref "CMP72")
      (value "2X2AND_OR")
      (footprint "eagle-import:2X2AND_OR")
      (libsource (lib "eagle-import") (part "2X2AND_OR"))
    )
    (comp (ref "CMP73")
      (value "2OR")
      (footprint "eagle-import:2OR")
      (libsource (lib "eagle-import") (part "2OR"))
    )
    (comp (ref "CMP74")
      (value "2X2AND_OR")
      (footprint "eagle-import:2X2AND_OR")
      (libsource (lib "eagle-import") (part "2X2AND_OR"))
    )
    (comp (ref "CMP18")
      (value "2OR")
      (footprint "eagle-import:2OR")
      (libsource (lib "eagle-import") (part "2OR"))
    )
    (comp (ref "CMP32")
      (value "2X2AND_OR")
      (footprint "eagle-import:2X2AND_OR")
      (libsource (lib "eagle-import") (part "2X2AND_OR"))
    )
    (comp (ref "CMP33")
      (value "2X2AND_OR")
      (footprint "eagle-import:2X2AND_OR")
      (libsource (lib "eagle-import") (part "2X2AND_OR"))
    )
    (comp (ref "CMP65")
      (value "2AND")
      (footprint "eagle-import:2AND")
      (libsource (lib "eagle-import") (part "2AND"))
    )
    (comp (ref "CMP66")
      (value "3OR")
      (footprint "eagle-import:3OR")
      (libsource (lib "eagle-import") (part "3OR"))
    )
    (comp (ref "CMP67")
      (value "8X2AND_OR")
      (footprint "eagle-import:8X2AND_OR")
      (libsource (lib "eagle-import") (part "8X2AND_OR"))
    )
    (comp (ref "CMP2")
      (value "4X2AND_OR")
      (footprint "eagle-import:4X2AND_OR")
      (libsource (lib "eagle-import") (part "4X2AND_OR"))
    )
    (comp (ref "CMP43")
      (value "3OR")
      (footprint "eagle-import:3OR")
      (libsource (lib "eagle-import") (part "3OR"))
    )
    (comp (ref "CMP11")
      (value "4OR")
      (footprint "eagle-import:4OR")
      (libsource (lib "eagle-import") (part "4OR"))
    )
    (comp (ref "CMP59")
      (value "4OR")
      (footprint "eagle-import:4OR")
      (libsource (lib "eagle-import") (part "4OR"))
    )
    (comp (ref "CMP61")
      (value "2X2AND_OR")
      (footprint "eagle-import:2X2AND_OR")
      (libsource (lib "eagle-import") (part "2X2AND_OR"))
    )
    (comp (ref "CMP63")
      (value "2OR")
      (footprint "eagle-import:2OR")
      (libsource (lib "eagle-import") (part "2OR"))
    )
    (comp (ref "CMP64")
      (value "4X2AND_OR")
      (footprint "eagle-import:4X2AND_OR")
      (libsource (lib "eagle-import") (part "4X2AND_OR"))
    )
    (comp (ref "CMP5")
      (value "4OR")
      (footprint "eagle-import:4OR")
      (libsource (lib "eagle-import") (part "4OR"))
    )
    (comp (ref "CMP56")
      (value "5OR")
      (footprint "eagle-import:5OR")
      (libsource (lib "eagle-import") (part "5OR"))
    )
    (comp (ref "CMP57")
      (value "4X2AND_OR")
      (footprint "eagle-import:4X2AND_OR")
      (libsource (lib "eagle-import") (part "4X2AND_OR"))
    )
    (comp (ref "CMP68")
      (value "2X2AND_OR")
      (footprint "eagle-import:2X2AND_OR")
      (libsource (lib "eagle-import") (part "2X2AND_OR"))
    )
    (comp (ref "CMP69")
      (value "2X2AND_OR")
      (footprint "eagle-import:2X2AND_OR")
      (libsource (lib "eagle-import") (part "2X2AND_OR"))
    )
    (comp (ref "CMP70")
      (value "2AND")
      (footprint "eagle-import:2AND")
      (libsource (lib "eagle-import") (part "2AND"))
    )
    (comp (ref "CMP75")
      (value "1BUF")
      (footprint "eagle-import:1BUF")
      (libsource (lib "eagle-import") (part "1BUF"))
    )
    (comp (ref "CMP4")
      (value "BUS_SPLIT_DISPLAY")
      (footprint "eagle-import:BUS_SPLIT_DISPLAY")
      (libsource (lib "eagle-import") (part "BUS_SPLIT_DISPLAY"))
    )
    (comp (ref "CMP15")
      (value "BUS_CONSTRUCT_DISPLAY")
      (footprint "eagle-import:BUS_SPLIT_DISPLAY")
      (libsource (lib "eagle-import") (part "BUS_CONSTRUCT_DISPLAY"))
    )
    (comp (ref "CMP80")
      (value "BUS_SPLIT_DISPLAY")
      (footprint "eagle-import:BUS_SPLIT_DISPLAY")
      (libsource (lib "eagle-import") (part "BUS_SPLIT_DISPLAY"))
    )
    (comp (ref "CMP1")
      (value "5OR")
      (footprint "eagle-import:5OR")
      (libsource (lib "eagle-import") (part "5OR"))
    )
    (comp (ref "CMP13")
      (value "2AND")
      (footprint "eagle-import:2AND")
      (libsource (lib "eagle-import") (part "2AND"))
    )
    (comp (ref "CMP31")
      (value "2OR")
      (footprint "eagle-import:2OR")
      (libsource (lib "eagle-import") (part "2OR"))
    )
    (comp (ref "CMP34")
      (value "2AND")
      (footprint "eagle-import:2AND")
      (libsource (lib "eagle-import") (part "2AND"))
    )
    (comp (ref "CMP38")
      (value "2X2AND_OR")
      (footprint "eagle-import:2X2AND_OR")
      (libsource (lib "eagle-import") (part "2X2AND_OR"))
    )
    (comp (ref "CMP39")
      (value "2AND")
      (footprint "eagle-import:2AND")
      (libsource (lib "eagle-import") (part "2AND"))
    )
    (comp (ref "CMP3")
      (value "3OR")
      (footprint "eagle-import:3OR")
      (libsource (lib "eagle-import") (part "3OR"))
    )
    (comp (ref "CMP47")
      (value "3AND")
      (footprint "eagle-import:3AND")
      (libsource (lib "eagle-import") (part "3AND"))
    )
    (comp (ref "CMP49")
      (value "4X2AND_OR")
      (footprint "eagle-import:4X2AND_OR")
      (libsource (lib "eagle-import") (part "4X2AND_OR"))
    )
    (comp (ref "CMP53")
      (value "1BUF")
      (footprint "eagle-import:1BUF")
      (libsource (lib "eagle-import") (part "1BUF"))
    )
    (comp (ref "CMP9")
      (value "BUS_SPLIT_DISPLAY")
      (footprint "eagle-import:BUS_SPLIT_DISPLAY")
      (libsource (lib "eagle-import") (part "BUS_SPLIT_DISPLAY"))
    )
    (comp (ref "CMP10")
      (value "BUS_SPLIT_DISPLAY")
      (footprint "eagle-import:BUS_SPLIT_DISPLAY")
      (libsource (lib "eagle-import") (part "BUS_SPLIT_DISPLAY"))
    )
    (comp (ref "CMP12")
      (value "BUS_SPLIT_DISPLAY")
      (footprint "eagle-import:BUS_SPLIT_DISPLAY")
      (libsource (lib "eagle-import") (part "BUS_SPLIT_DISPLAY"))
    )
    (comp (ref "CMP14")
      (value "BUS_SPLIT_DISPLAY")
      (footprint "eagle-import:BUS_SPLIT_DISPLAY")
      (libsource (lib "eagle-import") (part "BUS_SPLIT_DISPLAY"))
    )
  )
  (nets
    (net (code "1") (name "ADD1_RESULT_IS_N") (class "Default")
      (node (ref "CMP49") (pin "P$5") (pinfunction "C0_P$5") (pintype "input"))
      (node (ref "CMP8") (pin "P$3") (pinfunction "OUT_2_P$3") (pintype "output"))
    )
    (net (code "2") (name "ADD2_ADD_C") (class "Default")
      (node (ref "CMP57") (pin "P$1") (pinfunction "A0_P$1") (pintype "input"))
      (node (ref "CMP8") (pin "P$9") (pinfunction "OUT_8_P$9") (pintype "output"))
    )
    (net (code "3") (name "ADD2_IS_Z") (class "Default")
      (node (ref "CMP6") (pin "P$11") (pinfunction "OUT_10_P$11") (pintype "output"))
      (node (ref "CMP67") (pin "P$5") (pinfunction "C0_P$5") (pintype "input"))
    )
    (net (code "4") (name "ADD2_LSB") (class "Default")
      (node (ref "CMP52") (pin "P$5") (pinfunction "C0_P$5") (pintype "input"))
      (node (ref "CMP6") (pin "P$12") (pinfunction "OUT_11_P$12") (pintype "output"))
    )
    (net (code "5") (name "ARITH_C") (class "Default")
      (node (ref "CMP52") (pin "P$15") (pinfunction "H1_P$15") (pintype "input"))
      (node (ref "CMP8") (pin "P$2") (pinfunction "OUT_1_P$2") (pintype "output"))
    )
    (net (code "6") (name "ARITH_V") (class "Default")
      (node (ref "CMP49") (pin "P$7") (pinfunction "D0_P$7") (pintype "input"))
      (node (ref "CMP8") (pin "P$1") (pinfunction "OUT_0_P$1") (pintype "output"))
    )
    (net (code "7") (name "BIT_SHIFT_MODE_ARITH") (class "Default")
      (node (ref "CMP47") (pin "P$1") (pinfunction "1_P$1") (pintype "input"))
      (node (ref "CMP80") (pin "P$6") (pinfunction "OUT_5_P$6") (pintype "output"))
    )
    (net (code "8") (name "BIT_SHIFT_MODE_X_ROT") (class "Default")
      (node (ref "CMP50") (pin "P$1") (pinfunction "0_P$1") (pintype "input"))
      (node (ref "CMP80") (pin "P$8") (pinfunction "OUT_7_P$8") (pintype "output"))
    )
    (net (code "9") (name "BIT_TEST_RESULT") (class "Default")
      (node (ref "CMP67") (pin "P$9") (pinfunction "E1_P$9") (pintype "input"))
      (node (ref "CMP8") (pin "P$5") (pinfunction "OUT_4_P$5") (pintype "output"))
    )
    (net (code "10") (name "BUS_DECODE_FLAGS_1") (class "Default")
      (node (ref "CMP4") (pin "INPUT") (pinfunction "INPUT_INPUT") (pintype "input"))
    )
    (net (code "11") (name "BUS_DECODE_FLAGS_2") (class "Default")
      (node (ref "CMP80") (pin "INPUT") (pinfunction "INPUT_INPUT") (pintype "input"))
    )
    (net (code "12") (name "BUS_H_D") (class "Default")
      (node (ref "CMP9") (pin "INPUT") (pinfunction "INPUT_INPUT") (pintype "input"))
    )
    (net (code "13") (name "BUS_INSTR") (class "Default")
      (node (ref "CMP10") (pin "INPUT") (pinfunction "INPUT_INPUT") (pintype "input"))
    )
    (net (code "14") (name "BUS_PS") (class "Default")
      (node (ref "CMP12") (pin "INPUT") (pinfunction "INPUT_INPUT") (pintype "input"))
    )
    (net (code "15") (name "BUS_RN_ARITH_FLAGS") (class "Default")
      (node (ref "CMP6") (pin "INPUT") (pinfunction "INPUT_INPUT") (pintype "input"))
    )
    (net (code "16") (name "BUS_STATE") (class "Default")
      (node (ref "CMP14") (pin "INPUT") (pinfunction "INPUT_INPUT") (pintype "input"))
    )
    (net (code "17") (name "DIV_BY_ZERO") (class "Default")
      (node (ref "CMP71") (pin "P$1") (pinfunction "A2_P$1") (pintype "input"))
      (node (ref "CMP72") (pin "P$3") (pinfunction "B0_P$3") (pintype "input"))
      (node (ref "CMP72") (pin "P$4") (pinfunction "B1_P$4") (pintype "input"))
      (node (ref "CMP80") (pin "P$10") (pinfunction "OUT_9_P$10") (pintype "output"))
    )
    (net (code "18") (name "FLAG_C") (class "Default")
      (node (ref "CMP12") (pin "P$6") (pinfunction "OUT_5_P$6") (pintype "output"))
      (node (ref "CMP52") (pin "P$7") (pinfunction "D0_P$7") (pintype "input"))
    )
    (net (code "19") (name "FLAG_D") (class "Default")
      (node (ref "CMP12") (pin "P$7") (pinfunction "OUT_6_P$7") (pintype "output"))
      (node (ref "CMP28") (pin "P$7") (pinfunction "IN_6_P$7") (pintype "input"))
    )
    (net (code "20") (name "FLAG_F0") (class "Default")
      (node (ref "CMP12") (pin "P$9") (pinfunction "OUT_8_P$9") (pintype "output"))
      (node (ref "CMP68") (pin "P$1") (pinfunction "A0_P$1") (pintype "input"))
    )
    (net (code "21") (name "FLAG_F1") (class "Default")
      (node (ref "CMP12") (pin "P$10") (pinfunction "OUT_9_P$10") (pintype "output"))
      (node (ref "CMP69") (pin "P$1") (pinfunction "A0_P$1") (pintype "input"))
    )
    (net (code "22") (name "FLAG_F2") (class "Default")
      (node (ref "CMP12") (pin "P$11") (pinfunction "OUT_10_P$11") (pintype "output"))
    )
    (net (code "23") (name "FLAG_F3") (class "Default")
      (node (ref "CMP12") (pin "P$12") (pinfunction "OUT_11_P$12") (pintype "output"))
    )
    (net (code "24") (name "FLAG_F4") (class "Default")
      (node (ref "CMP12") (pin "P$13") (pinfunction "OUT_12_P$13") (pintype "output"))
      (node (ref "CMP72") (pin "P$1") (pinfunction "A0_P$1") (pintype "input"))
    )
    (net (code "25") (name "FLAG_F5") (class "Default")
      (node (ref "CMP12") (pin "P$14") (pinfunction "OUT_13_P$14") (pintype "output"))
      (node (ref "CMP74") (pin "P$1") (pinfunction "A0_P$1") (pintype "input"))
    )
    (net (code "26") (name "FLAG_F6") (class "Default")
      (node (ref "CMP12") (pin "P$15") (pinfunction "OUT_14_P$15") (pintype "output"))
      (node (ref "CMP17") (pin "P$1") (pinfunction "A0_P$1") (pintype "input"))
      (node (ref "CMP7") (pin "IN") (pinfunction "IN_IN") (pintype "input"))
    )
    (net (code "27") (name "FLAG_F6_N") (class "Default")
      (node (ref "CMP50") (pin "P$4") (pinfunction "3_P$4") (pintype "input"))
      (node (ref "CMP7") (pin "N") (pinfunction "N_N") (pintype "output"))
    )
    (net (code "28") (name "FLAG_I") (class "Default")
      (node (ref "CMP12") (pin "P$1") (pinfunction "OUT_0_P$1") (pintype "output"))
      (node (ref "CMP39") (pin "P$2") (pinfunction "2_P$2") (pintype "input"))
    )
    (net (code "29") (name "FLAG_N") (class "Default")
      (node (ref "CMP12") (pin "P$2") (pinfunction "OUT_1_P$2") (pintype "output"))
      (node (ref "CMP64") (pin "P$1") (pinfunction "A0_P$1") (pintype "input"))
    )
    (net (code "30") (name "FLAG_U") (class "Default")
      (node (ref "CMP12") (pin "P$8") (pinfunction "OUT_7_P$8") (pintype "output"))
      (node (ref "CMP28") (pin "P$8") (pinfunction "IN_7_P$8") (pintype "input"))
    )
    (net (code "31") (name "FLAG_V") (class "Default")
      (node (ref "CMP12") (pin "P$4") (pinfunction "OUT_3_P$4") (pintype "output"))
      (node (ref "CMP31") (pin "P$1") (pinfunction "A2_P$1") (pintype "input"))
      (node (ref "CMP49") (pin "P$1") (pinfunction "A0_P$1") (pintype "input"))
    )
    (net (code "32") (name "FLAG_X") (class "Default")
      (node (ref "CMP12") (pin "P$5") (pinfunction "OUT_4_P$5") (pintype "output"))
      (node (ref "CMP52") (pin "P$9") (pinfunction "E1_P$9") (pintype "input"))
      (node (ref "CMP57") (pin "P$3") (pinfunction "B0_P$3") (pintype "input"))
    )
    (net (code "33") (name "FLAG_Z") (class "Default")
      (node (ref "CMP12") (pin "P$3") (pinfunction "OUT_2_P$3") (pintype "output"))
      (node (ref "CMP13") (pin "P$1") (pinfunction "1_P$1") (pintype "input"))
      (node (ref "CMP67") (pin "P$7") (pinfunction "D0_P$7") (pintype "input"))
    )
    (net (code "34") (name "HOLD_F0_F1") (class "Default")
      (node (ref "CMP68") (pin "P$2") (pinfunction "A1_P$2") (pintype "input"))
      (node (ref "CMP69") (pin "P$2") (pinfunction "A1_P$2") (pintype "input"))
      (node (ref "CMP75") (pin "N") (pinfunction "N_N") (pintype "output"))
    )
    (net (code "35") (name "HOLD_F6") (class "Default")
      (node (ref "CMP16") (pin "N") (pinfunction "N_N") (pintype "output"))
      (node (ref "CMP17") (pin "P$2") (pinfunction "A1_P$2") (pintype "input"))
      (node (ref "CMP17") (pin "P$3") (pinfunction "A2_P$3") (pintype "input"))
    )
    (net (code "36") (name "H_0") (class "Default")
      (node (ref "CMP9") (pin "P$1") (pinfunction "OUT_0_P$1") (pintype "output"))
    )
    (net (code "37") (name "H_1") (class "Default")
      (node (ref "CMP9") (pin "P$2") (pinfunction "OUT_1_P$2") (pintype "output"))
    )
    (net (code "38") (name "H_2") (class "Default")
      (node (ref "CMP9") (pin "P$3") (pinfunction "OUT_2_P$3") (pintype "output"))
    )
    (net (code "39") (name "H_3") (class "Default")
      (node (ref "CMP17") (pin "P$5") (pinfunction "B1_P$5") (pintype "input"))
      (node (ref "CMP9") (pin "P$4") (pinfunction "OUT_3_P$4") (pintype "output"))
    )
    (net (code "40") (name "H_4") (class "Default")
      (node (ref "CMP53") (pin "IN") (pinfunction "IN_IN") (pintype "input"))
      (node (ref "CMP9") (pin "P$5") (pinfunction "OUT_4_P$5") (pintype "output"))
    )
    (net (code "41") (name "H_4_N") (class "Default")
      (node (ref "CMP47") (pin "P$3") (pinfunction "3_P$3") (pintype "input"))
      (node (ref "CMP53") (pin "N") (pinfunction "N_N") (pintype "output"))
    )
    (net (code "42") (name "H_5") (class "Default")
      (node (ref "CMP17") (pin "P$4") (pinfunction "B0_P$4") (pintype "input"))
      (node (ref "CMP9") (pin "P$6") (pinfunction "OUT_5_P$6") (pintype "output"))
    )
    (net (code "43") (name "H_6") (class "Default")
      (node (ref "CMP9") (pin "P$7") (pinfunction "OUT_6_P$7") (pintype "output"))
    )
    (net (code "44") (name "H_7") (class "Default")
      (node (ref "CMP9") (pin "P$8") (pinfunction "OUT_7_P$8") (pintype "output"))
    )
    (net (code "45") (name "H_8") (class "Default")
      (node (ref "CMP9") (pin "P$9") (pinfunction "OUT_8_P$9") (pintype "output"))
    )
    (net (code "46") (name "H_9") (class "Default")
      (node (ref "CMP9") (pin "P$10") (pinfunction "OUT_9_P$10") (pintype "output"))
    )
    (net (code "47") (name "H_10") (class "Default")
      (node (ref "CMP9") (pin "P$11") (pinfunction "OUT_10_P$11") (pintype "output"))
    )
    (net (code "48") (name "H_11") (class "Default")
      (node (ref "CMP9") (pin "P$12") (pinfunction "OUT_11_P$12") (pintype "output"))
    )
    (net (code "49") (name "H_12") (class "Default")
      (node (ref "CMP9") (pin "P$13") (pinfunction "OUT_12_P$13") (pintype "output"))
    )
    (net (code "50") (name "H_13") (class "Default")
      (node (ref "CMP9") (pin "P$14") (pinfunction "OUT_13_P$14") (pintype "output"))
    )
    (net (code "51") (name "H_14") (class "Default")
      (node (ref "CMP9") (pin "P$15") (pinfunction "OUT_14_P$15") (pintype "output"))
    )
    (net (code "52") (name "H_15") (class "Default")
      (node (ref "CMP9") (pin "P$16") (pinfunction "OUT_15_P$16") (pintype "output"))
    )
    (net (code "53") (name "H_COUNT_IS_15") (class "Default")
      (node (ref "CMP70") (pin "P$1") (pinfunction "1_P$1") (pintype "input"))
      (node (ref "CMP80") (pin "P$9") (pinfunction "OUT_8_P$9") (pintype "output"))
    )
    (net (code "54") (name "INSTR_0") (class "Default")
      (node (ref "CMP10") (pin "P$1") (pinfunction "OUT_0_P$1") (pintype "output"))
      (node (ref "CMP15") (pin "P$2") (pinfunction "IN_1_P$2") (pintype "input"))
    )
    (net (code "55") (name "INSTR_0_N") (class "Default")
      (node (ref "CMP10") (pin "P$9") (pinfunction "OUT_8_P$9") (pintype "output"))
    )
    (net (code "56") (name "INSTR_1") (class "Default")
      (node (ref "CMP10") (pin "P$2") (pinfunction "OUT_1_P$2") (pintype "output"))
      (node (ref "CMP15") (pin "P$3") (pinfunction "IN_2_P$3") (pintype "input"))
    )
    (net (code "57") (name "INSTR_1_N") (class "Default")
      (node (ref "CMP10") (pin "P$10") (pinfunction "OUT_9_P$10") (pintype "output"))
    )
    (net (code "58") (name "INSTR_2") (class "Default")
      (node (ref "CMP10") (pin "P$3") (pinfunction "OUT_2_P$3") (pintype "output"))
      (node (ref "CMP15") (pin "P$4") (pinfunction "IN_3_P$4") (pintype "input"))
    )
    (net (code "59") (name "INSTR_2_N") (class "Default")
      (node (ref "CMP10") (pin "P$11") (pinfunction "OUT_10_P$11") (pintype "output"))
    )
    (net (code "60") (name "INSTR_3") (class "Default")
      (node (ref "CMP10") (pin "P$4") (pinfunction "OUT_3_P$4") (pintype "output"))
      (node (ref "CMP15") (pin "P$5") (pinfunction "IN_4_P$5") (pintype "input"))
      (node (ref "CMP61") (pin "P$4") (pinfunction "B1_P$4") (pintype "input"))
    )
    (net (code "61") (name "INSTR_3_N") (class "Default")
      (node (ref "CMP10") (pin "P$12") (pinfunction "OUT_11_P$12") (pintype "output"))
    )
    (net (code "62") (name "INSTR_4") (class "Default")
      (node (ref "CMP10") (pin "P$5") (pinfunction "OUT_4_P$5") (pintype "output"))
    )
    (net (code "63") (name "INSTR_4_N") (class "Default")
      (node (ref "CMP10") (pin "P$13") (pinfunction "OUT_12_P$13") (pintype "output"))
    )
    (net (code "64") (name "INSTR_5") (class "Default")
      (node (ref "CMP10") (pin "P$6") (pinfunction "OUT_5_P$6") (pintype "output"))
    )
    (net (code "65") (name "INSTR_5_N") (class "Default")
      (node (ref "CMP10") (pin "P$14") (pinfunction "OUT_13_P$14") (pintype "output"))
    )
    (net (code "66") (name "INSTR_6") (class "Default")
      (node (ref "CMP10") (pin "P$7") (pinfunction "OUT_6_P$7") (pintype "output"))
    )
    (net (code "67") (name "INSTR_6_N") (class "Default")
      (node (ref "CMP10") (pin "P$15") (pinfunction "OUT_14_P$15") (pintype "output"))
      (node (ref "CMP2") (pin "P$7") (pinfunction "D0_P$7") (pintype "input"))
    )
    (net (code "68") (name "INSTR_7") (class "Default")
      (node (ref "CMP10") (pin "P$8") (pinfunction "OUT_7_P$8") (pintype "output"))
    )
    (net (code "69") (name "IS_SIMPLE_REG_TO_REG") (class "Default")
      (node (ref "CMP10") (pin "P$16") (pinfunction "OUT_15_P$16") (pintype "output"))
      (node (ref "CMP59") (pin "4") (pinfunction "3_4") (pintype "input"))
    )
    (net (code "70") (name "LDI_X_STATE_0_BYTE_1_WORD") (class "Default")
      (node (ref "CMP59") (pin "2") (pinfunction "1_2") (pintype "input"))
      (node (ref "CMP80") (pin "P$2") (pinfunction "OUT_1_P$2") (pintype "output"))
    )
    (net (code "71") (name "LOAD_F0_F1") (class "Default")
      (node (ref "CMP68") (pin "P$4") (pinfunction "B1_P$4") (pintype "input"))
      (node (ref "CMP69") (pin "P$3") (pinfunction "B0_P$3") (pintype "input"))
      (node (ref "CMP75") (pin "P") (pinfunction "P_P") (pintype "output"))
    )
    (net (code "72") (name "LOAD_F6") (class "Default")
      (node (ref "CMP16") (pin "P") (pinfunction "P_P") (pintype "output"))
      (node (ref "CMP17") (pin "P$6") (pinfunction "B2_P$6") (pintype "input"))
    )
    (net (code "73") (name "LOAD_WEIGHT") (class "Default")
      (node (ref "CMP11") (pin "4") (pinfunction "3_4") (pintype "input"))
      (node (ref "CMP3") (pin "P$1") (pinfunction "0_P$1") (pintype "input"))
      (node (ref "CMP51") (pin "2") (pinfunction "1_2") (pintype "input"))
      (node (ref "CMP52") (pin "P$6") (pinfunction "C1_P$6") (pintype "input"))
      (node (ref "CMP56") (pin "3") (pinfunction "2_3") (pintype "input"))
      (node (ref "CMP67") (pin "P$6") (pinfunction "C1_P$6") (pintype "input"))
      (node (ref "CMP80") (pin "P$4") (pinfunction "OUT_3_P$4") (pintype "output"))
    )
    (net (code "74") (name "MAIN_RN_INPUT_MUX_IS_N") (class "Default")
      (node (ref "CMP6") (pin "P$9") (pinfunction "OUT_8_P$9") (pintype "output"))
      (node (ref "CMP64") (pin "P$5") (pinfunction "C0_P$5") (pintype "input"))
      (node (ref "CMP64") (pin "P$7") (pinfunction "D0_P$7") (pintype "input"))
    )
    (net (code "75") (name "MAIN_RN_INPUT_MUX_IS_Z") (class "Default")
      (node (ref "CMP13") (pin "P$2") (pinfunction "2_P$2") (pintype "input"))
      (node (ref "CMP6") (pin "P$10") (pinfunction "OUT_9_P$10") (pintype "output"))
      (node (ref "CMP67") (pin "P$15") (pinfunction "H1_P$15") (pintype "input"))
    )
    (net (code "76") (name "MAIN_RN_INPUT_MUX_IS_Z_EXTENDED") (class "Default")
      (node (ref "CMP13") (pin "OUT_P") (pinfunction "P_OUT_P") (pintype "output"))
      (node (ref "CMP67") (pin "P$14") (pinfunction "G2_P$14") (pintype "input"))
    )
    (net (code "77") (name "NEXT_C_MUX_HOLD") (class "Default")
      (node (ref "CMP51") (pin "OUT_M") (pinfunction "N_OUT_M") (pintype "output"))
      (node (ref "CMP52") (pin "P$8") (pinfunction "D1_P$8") (pintype "input"))
    )
    (net (code "78") (name "NEXT_C_MUX_X") (class "Default")
      (node (ref "CMP50") (pin "OUT_P") (pinfunction "P_OUT_P") (pintype "output"))
      (node (ref "CMP51") (pin "1") (pinfunction "0_1") (pintype "input"))
      (node (ref "CMP52") (pin "P$10") (pinfunction "E2_P$10") (pintype "input"))
    )
    (net (code "79") (name "NEXT_C_SPECIFIC") (class "Default")
      (node (ref "CMP28") (pin "P$6") (pinfunction "IN_5_P$6") (pintype "input"))
      (node (ref "CMP52") (pin "OUT_P") (pinfunction "P_OUT_P") (pintype "output"))
      (node (ref "CMP57") (pin "P$5") (pinfunction "C0_P$5") (pintype "input"))
    )
    (net (code "80") (name "NEXT_F0_SPECIFIC") (class "Default")
      (node (ref "CMP28") (pin "P$9") (pinfunction "IN_8_P$9") (pintype "input"))
      (node (ref "CMP68") (pin "OUT_P") (pinfunction "P_OUT_P") (pintype "output"))
    )
    (net (code "81") (name "NEXT_F1_SPECIFIC") (class "Default")
      (node (ref "CMP28") (pin "P$10") (pinfunction "IN_9_P$10") (pintype "input"))
      (node (ref "CMP69") (pin "OUT_P") (pinfunction "P_OUT_P") (pintype "output"))
    )
    (net (code "82") (name "NEXT_F3_SPECIFIC") (class "Default")
      (node (ref "CMP28") (pin "P$12") (pinfunction "IN_11_P$12") (pintype "input"))
      (node (ref "CMP70") (pin "OUT_P") (pinfunction "P_OUT_P") (pintype "output"))
    )
    (net (code "83") (name "NEXT_F4_HOLD") (class "Default")
      (node (ref "CMP71") (pin "OUT_M") (pinfunction "N_OUT_M") (pintype "output"))
      (node (ref "CMP72") (pin "P$2") (pinfunction "A1_P$2") (pintype "input"))
    )
    (net (code "84") (name "NEXT_F4_SPECIFIC") (class "Default")
      (node (ref "CMP28") (pin "P$13") (pinfunction "IN_12_P$13") (pintype "input"))
      (node (ref "CMP72") (pin "OUT_P") (pinfunction "P_OUT_P") (pintype "output"))
    )
    (net (code "85") (name "NEXT_F5_HOLD") (class "Default")
      (node (ref "CMP73") (pin "OUT_M") (pinfunction "N_OUT_M") (pintype "output"))
      (node (ref "CMP74") (pin "P$2") (pinfunction "A1_P$2") (pintype "input"))
    )
    (net (code "86") (name "NEXT_F5_SPECIFIC") (class "Default")
      (node (ref "CMP28") (pin "P$14") (pinfunction "IN_13_P$14") (pintype "input"))
      (node (ref "CMP74") (pin "OUT_P") (pinfunction "P_OUT_P") (pintype "output"))
    )
    (net (code "87") (name "NEXT_F6_SPECIFIC") (class "Default")
      (node (ref "CMP17") (pin "OUT_P") (pinfunction "P_OUT_P") (pintype "output"))
      (node (ref "CMP28") (pin "P$15") (pinfunction "IN_14_P$15") (pintype "input"))
    )
    (net (code "88") (name "NEXT_I_MUX_HOLD") (class "Default")
      (node (ref "CMP38") (pin "OUT_M") (pinfunction "N_OUT_M") (pintype "output"))
      (node (ref "CMP39") (pin "P$1") (pinfunction "1_P$1") (pintype "input"))
    )
    (net (code "89") (name "NEXT_I_SPECIFIC") (class "Default")
      (node (ref "CMP28") (pin "P$1") (pinfunction "IN_0_P$1") (pintype "input"))
      (node (ref "CMP39") (pin "OUT_P") (pinfunction "P_OUT_P") (pintype "output"))
    )
    (net (code "90") (name "NEXT_NZ_MUX_COMMON") (class "Default")
      (node (ref "CMP11") (pin "OUT_P") (pinfunction "P_OUT_P") (pintype "output"))
      (node (ref "CMP63") (pin "P$2") (pinfunction "A1_P$2") (pintype "input"))
      (node (ref "CMP66") (pin "P$1") (pinfunction "0_P$1") (pintype "input"))
    )
    (net (code "91") (name "NEXT_NZ_MUX_MAIN") (class "Default")
      (node (ref "CMP11") (pin "2") (pinfunction "1_2") (pintype "input"))
      (node (ref "CMP59") (pin "OUT_P") (pinfunction "P_OUT_P") (pintype "output"))
      (node (ref "CMP64") (pin "P$8") (pinfunction "D1_P$8") (pintype "input"))
      (node (ref "CMP67") (pin "P$16") (pinfunction "H2_P$16") (pintype "input"))
    )
    (net (code "92") (name "NEXT_NZ_MUX_RAC") (class "Default")
      (node (ref "CMP11") (pin "1") (pinfunction "0_1") (pintype "input"))
      (node (ref "CMP61") (pin "OUT_P") (pinfunction "P_OUT_P") (pintype "output"))
      (node (ref "CMP64") (pin "P$4") (pinfunction "B1_P$4") (pintype "input"))
      (node (ref "CMP67") (pin "P$12") (pinfunction "F2_P$12") (pintype "input"))
    )
    (net (code "93") (name "NEXT_N_MUX_HOLD") (class "Default")
      (node (ref "CMP63") (pin "OUT_M") (pinfunction "N_OUT_M") (pintype "output"))
      (node (ref "CMP64") (pin "P$2") (pinfunction "A1_P$2") (pintype "input"))
    )
    (net (code "94") (name "NEXT_N_SPECIFIC") (class "Default")
      (node (ref "CMP28") (pin "P$2") (pinfunction "IN_1_P$2") (pintype "input"))
      (node (ref "CMP64") (pin "OUT_P") (pinfunction "P_OUT_P") (pintype "output"))
    )
    (net (code "95") (name "NEXT_SPECIFIC") (class "Default")
      (node (ref "CMP28") (pin "INPUT") (pinfunction "OUT_INPUT") (pintype "output"))
    )
    (net (code "96") (name "NEXT_VC_MUX_ARITH") (class "Default")
      (node (ref "CMP1") (pin "OUT_P") (pinfunction "P_OUT_P") (pintype "output"))
      (node (ref "CMP43") (pin "P$3") (pinfunction "2_P$3") (pintype "input"))
      (node (ref "CMP49") (pin "P$8") (pinfunction "D1_P$8") (pintype "input"))
      (node (ref "CMP52") (pin "P$16") (pinfunction "H2_P$16") (pintype "input"))
    )
    (net (code "97") (name "NEXT_VC_MUX_CLEAR") (class "Default")
      (node (ref "CMP2") (pin "OUT_P") (pinfunction "P_OUT_P") (pintype "output"))
      (node (ref "CMP43") (pin "P$1") (pinfunction "0_P$1") (pintype "input"))
    )
    (net (code "98") (name "NEXT_VC_MUX_CLEAR__MISC_OPTIONS") (class "Default")
      (node (ref "CMP2") (pin "P$5") (pinfunction "C0_P$5") (pintype "input"))
      (node (ref "CMP4") (pin "P$6") (pinfunction "OUT_5_P$6") (pintype "output"))
    )
    (net (code "99") (name "NEXT_VC_MUX_COMMON") (class "Default")
      (node (ref "CMP3") (pin "P$3") (pinfunction "2_P$3") (pintype "input"))
      (node (ref "CMP43") (pin "OUT_P") (pinfunction "P_OUT_P") (pintype "output"))
      (node (ref "CMP51") (pin "3") (pinfunction "2_3") (pintype "input"))
    )
    (net (code "100") (name "NEXT_V_MUX_ASL") (class "Default")
      (node (ref "CMP3") (pin "P$2") (pinfunction "1_P$2") (pintype "input"))
      (node (ref "CMP47") (pin "OUT_P") (pinfunction "P_OUT_P") (pintype "output"))
      (node (ref "CMP49") (pin "P$4") (pinfunction "B1_P$4") (pintype "input"))
    )
    (net (code "101") (name "NEXT_V_MUX_HOLD") (class "Default")
      (node (ref "CMP3") (pin "OUT_M") (pinfunction "N_OUT_M") (pintype "output"))
      (node (ref "CMP49") (pin "P$2") (pinfunction "A1_P$2") (pintype "input"))
    )
    (net (code "102") (name "NEXT_V_SPECIFIC") (class "Default")
      (node (ref "CMP28") (pin "P$4") (pinfunction "IN_3_P$4") (pintype "input"))
      (node (ref "CMP49") (pin "OUT_P") (pinfunction "P_OUT_P") (pintype "output"))
    )
    (net (code "103") (name "NEXT_XNZVC_MUX_CPLX_CLR") (class "Default")
      (node (ref "CMP34") (pin "OUT_P") (pinfunction "P_OUT_P") (pintype "output"))
      (node (ref "CMP56") (pin "1") (pinfunction "0_1") (pintype "input"))
      (node (ref "CMP63") (pin "P$1") (pinfunction "A2_P$1") (pintype "input"))
      (node (ref "CMP66") (pin "P$2") (pinfunction "1_P$2") (pintype "input"))
    )
    (net (code "104") (name "NEXT_XNZVC_MUX_LOGIC") (class "Default")
      (node (ref "CMP15") (pin "P$10") (pinfunction "IN_9_P$10") (pintype "input"))
      (node (ref "CMP18") (pin "P$2") (pinfunction "A1_P$2") (pintype "input"))
      (node (ref "CMP32") (pin "OUT_P") (pinfunction "P_OUT_P") (pintype "output"))
    )
    (net (code "105") (name "NEXT_XNZVC_MUX_MEMORY") (class "Default")
      (node (ref "CMP15") (pin "P$9") (pinfunction "IN_8_P$9") (pintype "input"))
      (node (ref "CMP18") (pin "P$1") (pinfunction "A2_P$1") (pintype "input"))
      (node (ref "CMP33") (pin "OUT_P") (pinfunction "P_OUT_P") (pintype "output"))
    )
    (net (code "106") (name "NEXT_XNZVC_MUX_SPECIFIC") (class "Default")
      (node (ref "CMP15") (pin "P$8") (pinfunction "IN_7_P$8") (pintype "input"))
      (node (ref "CMP18") (pin "OUT_M") (pinfunction "N_OUT_M") (pintype "output"))
    )
    (net (code "107") (name "NEXT_X_MUX_HOLD") (class "Default")
      (node (ref "CMP56") (pin "OUT_M") (pinfunction "N_OUT_M") (pintype "output"))
      (node (ref "CMP57") (pin "P$4") (pinfunction "B1_P$4") (pintype "input"))
    )
    (net (code "108") (name "NEXT_X_MUX_UPDATE") (class "Default")
      (node (ref "CMP5") (pin "OUT_P") (pinfunction "P_OUT_P") (pintype "output"))
      (node (ref "CMP56") (pin "4") (pinfunction "3_4") (pintype "input"))
      (node (ref "CMP57") (pin "P$6") (pinfunction "C1_P$6") (pintype "input"))
    )
    (net (code "109") (name "NEXT_X_SPECIFIC") (class "Default")
      (node (ref "CMP28") (pin "P$5") (pinfunction "IN_4_P$5") (pintype "input"))
      (node (ref "CMP57") (pin "OUT_P") (pinfunction "P_OUT_P") (pintype "output"))
    )
    (net (code "110") (name "NEXT_Z_HOLD") (class "Default")
      (node (ref "CMP66") (pin "OUT_M") (pinfunction "N_OUT_M") (pintype "output"))
      (node (ref "CMP67") (pin "P$8") (pinfunction "D1_P$8") (pintype "input"))
    )
    (net (code "111") (name "NEXT_Z_MUX_BIT_TEST") (class "Default")
      (node (ref "CMP65") (pin "OUT_P") (pinfunction "P_OUT_P") (pintype "output"))
      (node (ref "CMP66") (pin "P$3") (pinfunction "2_P$3") (pintype "input"))
      (node (ref "CMP67") (pin "P$10") (pinfunction "E2_P$10") (pintype "input"))
    )
    (net (code "112") (name "NEXT_Z_SPECIFIC") (class "Default")
      (node (ref "CMP28") (pin "P$3") (pinfunction "IN_2_P$3") (pintype "input"))
      (node (ref "CMP67") (pin "OUT_P") (pinfunction "P_OUT_P") (pintype "output"))
    )
    (net (code "113") (name "Net-(CMP2-B0)") (class "Default")
      (node (ref "CMP2") (pin "P$3") (pinfunction "B0_P$3") (pintype "input"))
      (node (ref "CMP2") (pin "P$4") (pinfunction "B1_P$4") (pintype "input"))
    )
    (net (code "114") (name "Net-(CMP52-A0)") (class "Default")
      (node (ref "CMP52") (pin "P$1") (pinfunction "A0_P$1") (pintype "input"))
      (node (ref "CMP52") (pin "P$2") (pinfunction "A1_P$2") (pintype "input"))
      (node (ref "CMP52") (pin "P$3") (pinfunction "B0_P$3") (pintype "input"))
      (node (ref "CMP52") (pin "P$4") (pinfunction "B1_P$4") (pintype "input"))
    )
    (net (code "115") (name "Net-(CMP67-A0)") (class "Default")
      (node (ref "CMP67") (pin "P$1") (pinfunction "A0_P$1") (pintype "input"))
      (node (ref "CMP67") (pin "P$2") (pinfunction "A1_P$2") (pintype "input"))
      (node (ref "CMP67") (pin "P$3") (pinfunction "B0_P$3") (pintype "input"))
      (node (ref "CMP67") (pin "P$4") (pinfunction "B1_P$4") (pintype "input"))
    )
    (net (code "116") (name "OPCODE_IS_ABS") (class "Default")
      (node (ref "CMP4") (pin "P$13") (pinfunction "OUT_12_P$13") (pintype "output"))
      (node (ref "CMP43") (pin "P$2") (pinfunction "1_P$2") (pintype "input"))
      (node (ref "CMP49") (pin "P$6") (pinfunction "C1_P$6") (pintype "input"))
      (node (ref "CMP52") (pin "P$14") (pinfunction "G2_P$14") (pintype "input"))
      (node (ref "CMP56") (pin "5") (pinfunction "4_5") (pintype "input"))
      (node (ref "CMP57") (pin "P$8") (pinfunction "D1_P$8") (pintype "input"))
    )
    (net (code "117") (name "OPCODE_IS_ADD_ADDQ") (class "Default")
      (node (ref "CMP1") (pin "4") (pinfunction "3_4") (pintype "input"))
      (node (ref "CMP4") (pin "P$9") (pinfunction "OUT_8_P$9") (pintype "output"))
      (node (ref "CMP5") (pin "2") (pinfunction "1_2") (pintype "input"))
    )
    (net (code "118") (name "OPCODE_IS_ANDI_PS") (class "Default")
      (node (ref "CMP15") (pin "P$7") (pinfunction "IN_6_P$7") (pintype "input"))
      (node (ref "CMP32") (pin "P$3") (pinfunction "B0_P$3") (pintype "input"))
      (node (ref "CMP4") (pin "P$4") (pinfunction "OUT_3_P$4") (pintype "output"))
    )
    (net (code "119") (name "OPCODE_IS_BIT_XX") (class "Default")
      (node (ref "CMP65") (pin "P$1") (pinfunction "1_P$1") (pintype "input"))
      (node (ref "CMP80") (pin "P$5") (pinfunction "OUT_4_P$5") (pintype "output"))
    )
    (net (code "120") (name "OPCODE_IS_BRANCH_GROUP") (class "Default")
      (node (ref "CMP15") (pin "P$1") (pinfunction "IN_0_P$1") (pintype "input"))
      (node (ref "CMP4") (pin "P$1") (pinfunction "OUT_0_P$1") (pintype "output"))
    )
    (net (code "121") (name "OPCODE_IS_CMP") (class "Default")
      (node (ref "CMP1") (pin "2") (pinfunction "1_2") (pintype "input"))
      (node (ref "CMP4") (pin "P$8") (pinfunction "OUT_7_P$8") (pintype "output"))
    )
    (net (code "122") (name "OPCODE_IS_LD_ST_STATE_0") (class "Default")
      (node (ref "CMP4") (pin "P$16") (pinfunction "OUT_15_P$16") (pintype "output"))
      (node (ref "CMP61") (pin "P$3") (pinfunction "B0_P$3") (pintype "input"))
    )
    (net (code "123") (name "OPCODE_IS_LD_ST_STATE_5") (class "Default")
      (node (ref "CMP59") (pin "1") (pinfunction "0_1") (pintype "input"))
      (node (ref "CMP80") (pin "P$1") (pinfunction "OUT_0_P$1") (pintype "output"))
    )
    (net (code "124") (name "OPCODE_IS_MUL_SQRT_DIV") (class "Default")
      (node (ref "CMP2") (pin "P$1") (pinfunction "A0_P$1") (pintype "input"))
      (node (ref "CMP34") (pin "P$2") (pinfunction "2_P$2") (pintype "input"))
      (node (ref "CMP4") (pin "P$5") (pinfunction "OUT_4_P$5") (pintype "output"))
    )
    (net (code "125") (name "OPCODE_IS_NEG") (class "Default")
      (node (ref "CMP1") (pin "1") (pinfunction "0_1") (pintype "input"))
      (node (ref "CMP4") (pin "P$7") (pinfunction "OUT_6_P$7") (pintype "output"))
    )
    (net (code "126") (name "OPCODE_IS_ORI_PS") (class "Default")
      (node (ref "CMP15") (pin "P$6") (pinfunction "IN_5_P$6") (pintype "input"))
      (node (ref "CMP32") (pin "P$1") (pinfunction "A0_P$1") (pintype "input"))
      (node (ref "CMP4") (pin "P$3") (pinfunction "OUT_2_P$3") (pintype "output"))
    )
    (net (code "127") (name "OPCODE_IS_POP_PS") (class "Default")
      (node (ref "CMP33") (pin "P$4") (pinfunction "B1_P$4") (pintype "input"))
      (node (ref "CMP4") (pin "P$2") (pinfunction "OUT_1_P$2") (pintype "output"))
    )
    (net (code "128") (name "OPCODE_IS_SHIFT_XX") (class "Default")
      (node (ref "CMP4") (pin "P$15") (pinfunction "OUT_14_P$15") (pintype "output"))
      (node (ref "CMP50") (pin "P$2") (pinfunction "1_P$2") (pintype "input"))
      (node (ref "CMP61") (pin "P$1") (pinfunction "A0_P$1") (pintype "input"))
    )
    (net (code "129") (name "OPCODE_IS_SUB") (class "Default")
      (node (ref "CMP1") (pin "3") (pinfunction "2_3") (pintype "input"))
      (node (ref "CMP4") (pin "P$11") (pinfunction "OUT_10_P$11") (pintype "output"))
    )
    (net (code "130") (name "OPCODE_IS_SUB_GROUP") (class "Default")
      (node (ref "CMP4") (pin "P$10") (pinfunction "OUT_9_P$10") (pintype "output"))
      (node (ref "CMP5") (pin "4") (pinfunction "3_4") (pintype "input"))
    )
    (net (code "131") (name "OPCODE_IS_TRAP") (class "Default")
      (node (ref "CMP38") (pin "P$2") (pinfunction "A1_P$2") (pintype "input"))
      (node (ref "CMP38") (pin "P$3") (pinfunction "B0_P$3") (pintype "input"))
      (node (ref "CMP4") (pin "P$14") (pinfunction "OUT_13_P$14") (pintype "output"))
    )
    (net (code "132") (name "OPCODE_IS_X_ARITH") (class "Default")
      (node (ref "CMP1") (pin "5") (pinfunction "4_5") (pintype "input"))
      (node (ref "CMP11") (pin "3") (pinfunction "2_3") (pintype "input"))
      (node (ref "CMP4") (pin "P$12") (pinfunction "OUT_11_P$12") (pintype "output"))
      (node (ref "CMP5") (pin "1") (pinfunction "0_1") (pintype "input"))
      (node (ref "CMP64") (pin "P$6") (pinfunction "C1_P$6") (pintype "input"))
      (node (ref "CMP67") (pin "P$13") (pinfunction "G1_P$13") (pintype "input"))
    )
    (net (code "133") (name "R0_IS_N") (class "Default")
      (node (ref "CMP6") (pin "P$1") (pinfunction "OUT_0_P$1") (pintype "output"))
      (node (ref "CMP68") (pin "P$3") (pinfunction "B0_P$3") (pintype "input"))
    )
    (net (code "134") (name "R0_IS_Z") (class "Default")
      (node (ref "CMP6") (pin "P$5") (pinfunction "OUT_4_P$5") (pintype "output"))
    )
    (net (code "135") (name "R1_IS_N") (class "Default")
      (node (ref "CMP6") (pin "P$2") (pinfunction "OUT_1_P$2") (pintype "output"))
      (node (ref "CMP69") (pin "P$4") (pinfunction "B1_P$4") (pintype "input"))
    )
    (net (code "136") (name "R1_IS_Z") (class "Default")
      (node (ref "CMP6") (pin "P$6") (pinfunction "OUT_5_P$6") (pintype "output"))
    )
    (net (code "137") (name "R2_IS_N") (class "Default")
      (node (ref "CMP6") (pin "P$3") (pinfunction "OUT_2_P$3") (pintype "output"))
    )
    (net (code "138") (name "R2_IS_Z") (class "Default")
      (node (ref "CMP6") (pin "P$7") (pinfunction "OUT_6_P$7") (pintype "output"))
    )
    (net (code "139") (name "R3_IS_N") (class "Default")
      (node (ref "CMP6") (pin "P$4") (pinfunction "OUT_3_P$4") (pintype "output"))
    )
    (net (code "140") (name "R3_IS_Z") (class "Default")
      (node (ref "CMP6") (pin "P$8") (pinfunction "OUT_7_P$8") (pintype "output"))
    )
    (net (code "141") (name "RA_MUX_IS_N") (class "Default")
      (node (ref "CMP52") (pin "P$13") (pinfunction "G1_P$13") (pintype "input"))
      (node (ref "CMP57") (pin "P$7") (pinfunction "D0_P$7") (pintype "input"))
      (node (ref "CMP64") (pin "P$3") (pinfunction "B0_P$3") (pintype "input"))
      (node (ref "CMP8") (pin "P$8") (pinfunction "OUT_7_P$8") (pintype "output"))
    )
    (net (code "142") (name "RA_MUX_IS_Z") (class "Default")
      (node (ref "CMP67") (pin "P$11") (pinfunction "F1_P$11") (pintype "input"))
      (node (ref "CMP8") (pin "P$7") (pinfunction "OUT_6_P$7") (pintype "output"))
    )
    (net (code "143") (name "RESET_SIGNAL") (class "Default")
      (node (ref "CMP28") (pin "P$11") (pinfunction "IN_10_P$11") (pintype "input"))
    )
    (net (code "144") (name "SHIFTING_NOT_ROTATION") (class "Default")
      (node (ref "CMP5") (pin "3") (pinfunction "2_3") (pintype "input"))
      (node (ref "CMP80") (pin "P$7") (pinfunction "OUT_6_P$7") (pintype "output"))
    )
    (net (code "145") (name "SHIFT_IS_SHIFTING") (class "Default")
      (node (ref "CMP47") (pin "P$2") (pinfunction "2_P$2") (pintype "input"))
      (node (ref "CMP51") (pin "4") (pinfunction "3_4") (pintype "input"))
      (node (ref "CMP52") (pin "P$12") (pinfunction "F2_P$12") (pintype "input"))
      (node (ref "CMP59") (pin "3") (pinfunction "2_3") (pintype "input"))
      (node (ref "CMP80") (pin "P$3") (pinfunction "OUT_2_P$3") (pintype "output"))
    )
    (net (code "146") (name "SHIFT_RESULT_C_FLAG") (class "Default")
      (node (ref "CMP52") (pin "P$11") (pinfunction "F1_P$11") (pintype "input"))
      (node (ref "CMP8") (pin "P$4") (pinfunction "OUT_3_P$4") (pintype "output"))
    )
    (net (code "147") (name "SHIFT_RESULT_V_FLAG") (class "Default")
      (node (ref "CMP31") (pin "P$2") (pinfunction "A1_P$2") (pintype "input"))
      (node (ref "CMP8") (pin "P$6") (pinfunction "OUT_5_P$6") (pintype "output"))
    )
    (net (code "148") (name "STATE_0") (class "Default")
      (node (ref "CMP14") (pin "P$1") (pinfunction "OUT_0_P$1") (pintype "output"))
      (node (ref "CMP2") (pin "P$6") (pinfunction "C1_P$6") (pintype "input"))
      (node (ref "CMP2") (pin "P$8") (pinfunction "D1_P$8") (pintype "input"))
      (node (ref "CMP61") (pin "P$2") (pinfunction "A1_P$2") (pintype "input"))
      (node (ref "CMP75") (pin "IN") (pinfunction "IN_IN") (pintype "input"))
    )
    (net (code "149") (name "STATE_1") (class "Default")
      (node (ref "CMP14") (pin "P$2") (pinfunction "OUT_1_P$2") (pintype "output"))
      (node (ref "CMP16") (pin "IN") (pinfunction "IN_IN") (pintype "input"))
    )
    (net (code "150") (name "STATE_2") (class "Default")
      (node (ref "CMP14") (pin "P$3") (pinfunction "OUT_2_P$3") (pintype "output"))
    )
    (net (code "151") (name "STATE_3") (class "Default")
      (node (ref "CMP14") (pin "P$4") (pinfunction "OUT_3_P$4") (pintype "output"))
      (node (ref "CMP2") (pin "P$2") (pinfunction "A1_P$2") (pintype "input"))
      (node (ref "CMP32") (pin "P$2") (pinfunction "A1_P$2") (pintype "input"))
      (node (ref "CMP32") (pin "P$4") (pinfunction "B1_P$4") (pintype "input"))
      (node (ref "CMP34") (pin "P$1") (pinfunction "1_P$1") (pintype "input"))
      (node (ref "CMP38") (pin "P$4") (pinfunction "B1_P$4") (pintype "input"))
      (node (ref "CMP50") (pin "P$3") (pinfunction "2_P$3") (pintype "input"))
      (node (ref "CMP65") (pin "P$2") (pinfunction "2_P$2") (pintype "input"))
    )
    (net (code "152") (name "STATE_4") (class "Default")
      (node (ref "CMP14") (pin "P$5") (pinfunction "OUT_4_P$5") (pintype "output"))
    )
    (net (code "153") (name "STATE_5") (class "Default")
      (node (ref "CMP14") (pin "P$6") (pinfunction "OUT_5_P$6") (pintype "output"))
      (node (ref "CMP33") (pin "P$3") (pinfunction "B0_P$3") (pintype "input"))
    )
    (net (code "154") (name "STATE_6") (class "Default")
      (node (ref "CMP14") (pin "P$7") (pinfunction "OUT_6_P$7") (pintype "output"))
    )
    (net (code "155") (name "STATE_7") (class "Default")
      (node (ref "CMP14") (pin "P$8") (pinfunction "OUT_7_P$8") (pintype "output"))
    )
    (net (code "156") (name "STATE_8") (class "Default")
      (node (ref "CMP14") (pin "P$9") (pinfunction "OUT_8_P$9") (pintype "output"))
      (node (ref "CMP33") (pin "P$1") (pinfunction "A0_P$1") (pintype "input"))
      (node (ref "CMP33") (pin "P$2") (pinfunction "A1_P$2") (pintype "input"))
    )
    (net (code "157") (name "STATE_9") (class "Default")
      (node (ref "CMP14") (pin "P$10") (pinfunction "OUT_9_P$10") (pintype "output"))
      (node (ref "CMP38") (pin "P$1") (pinfunction "A0_P$1") (pintype "input"))
    )
    (net (code "158") (name "STATE_10") (class "Default")
      (node (ref "CMP14") (pin "P$11") (pinfunction "OUT_10_P$11") (pintype "output"))
    )
    (net (code "159") (name "STATE_11") (class "Default")
      (node (ref "CMP14") (pin "P$12") (pinfunction "OUT_11_P$12") (pintype "output"))
    )
    (net (code "160") (name "STATE_12") (class "Default")
      (node (ref "CMP14") (pin "P$13") (pinfunction "OUT_12_P$13") (pintype "output"))
    )
    (net (code "161") (name "STATE_13") (class "Default")
      (node (ref "CMP14") (pin "P$14") (pinfunction "OUT_13_P$14") (pintype "output"))
      (node (ref "CMP56") (pin "2") (pinfunction "1_2") (pintype "input"))
      (node (ref "CMP57") (pin "P$2") (pinfunction "A1_P$2") (pintype "input"))
      (node (ref "CMP70") (pin "P$2") (pinfunction "2_P$2") (pintype "input"))
    )
    (net (code "162") (name "STATE_14") (class "Default")
      (node (ref "CMP14") (pin "P$15") (pinfunction "OUT_14_P$15") (pintype "output"))
    )
    (net (code "163") (name "STATE_15") (class "Default")
      (node (ref "CMP14") (pin "P$16") (pinfunction "OUT_15_P$16") (pintype "output"))
    )
    (net (code "164") (name "STICKY_V") (class "Default")
      (node (ref "CMP31") (pin "OUT_P") (pinfunction "P_OUT_P") (pintype "output"))
      (node (ref "CMP49") (pin "P$3") (pinfunction "B0_P$3") (pintype "input"))
    )
    (net (code "165") (name "TAKE_INTERRUPT") (class "Default")
      (node (ref "CMP73") (pin "P$2") (pinfunction "A1_P$2") (pintype "input"))
      (node (ref "CMP74") (pin "P$3") (pinfunction "B0_P$3") (pintype "input"))
      (node (ref "CMP74") (pin "P$4") (pinfunction "B1_P$4") (pintype "input"))
      (node (ref "CMP80") (pin "P$12") (pinfunction "OUT_11_P$12") (pintype "output"))
    )
    (net (code "166") (name "TRAP_STATE_7") (class "Default")
      (node (ref "CMP71") (pin "P$2") (pinfunction "A1_P$2") (pintype "input"))
      (node (ref "CMP73") (pin "P$1") (pinfunction "A2_P$1") (pintype "input"))
      (node (ref "CMP80") (pin "P$11") (pinfunction "OUT_10_P$11") (pintype "output"))
    )
    (net (code "167") (name "unconnected-(CMP1-N-PadOUT_M)") (class "Default")
      (node (ref "CMP1") (pin "OUT_M") (pinfunction "N_OUT_M") (pintype "output"))
    )
    (net (code "168") (name "unconnected-(CMP2-N-PadOUT_M)") (class "Default")
      (node (ref "CMP2") (pin "OUT_M") (pinfunction "N_OUT_M") (pintype "output"))
    )
    (net (code "169") (name "unconnected-(CMP3-P-PadOUT_P)") (class "Default")
      (node (ref "CMP3") (pin "OUT_P") (pinfunction "P_OUT_P") (pintype "output"))
    )
    (net (code "170") (name "unconnected-(CMP5-N-PadOUT_M)") (class "Default")
      (node (ref "CMP5") (pin "OUT_M") (pinfunction "N_OUT_M") (pintype "output"))
    )
    (net (code "171") (name "unconnected-(CMP6-OUT_12-PadP$13)") (class "Default")
      (node (ref "CMP6") (pin "P$13") (pinfunction "OUT_12_P$13") (pintype "output"))
    )
    (net (code "172") (name "unconnected-(CMP6-OUT_13-PadP$14)") (class "Default")
      (node (ref "CMP6") (pin "P$14") (pinfunction "OUT_13_P$14") (pintype "output"))
    )
    (net (code "173") (name "unconnected-(CMP6-OUT_14-PadP$15)") (class "Default")
      (node (ref "CMP6") (pin "P$15") (pinfunction "OUT_14_P$15") (pintype "output"))
    )
    (net (code "174") (name "unconnected-(CMP6-OUT_15-PadP$16)") (class "Default")
      (node (ref "CMP6") (pin "P$16") (pinfunction "OUT_15_P$16") (pintype "output"))
    )
    (net (code "175") (name "unconnected-(CMP7-PadP)") (class "Default")
      (node (ref "CMP7") (pin "P") (pinfunction "P_P") (pintype "output"))
    )
    (net (code "176") (name "unconnected-(CMP8-OUT_9-PadP$10)") (class "Default")
      (node (ref "CMP8") (pin "P$10") (pinfunction "OUT_9_P$10") (pintype "output"))
    )
    (net (code "177") (name "unconnected-(CMP8-OUT_10-PadP$11)") (class "Default")
      (node (ref "CMP8") (pin "P$11") (pinfunction "OUT_10_P$11") (pintype "output"))
    )
    (net (code "178") (name "unconnected-(CMP8-OUT_11-PadP$12)") (class "Default")
      (node (ref "CMP8") (pin "P$12") (pinfunction "OUT_11_P$12") (pintype "output"))
    )
    (net (code "179") (name "unconnected-(CMP8-OUT_12-PadP$13)") (class "Default")
      (node (ref "CMP8") (pin "P$13") (pinfunction "OUT_12_P$13") (pintype "output"))
    )
    (net (code "180") (name "unconnected-(CMP8-OUT_13-PadP$14)") (class "Default")
      (node (ref "CMP8") (pin "P$14") (pinfunction "OUT_13_P$14") (pintype "output"))
    )
    (net (code "181") (name "unconnected-(CMP8-OUT_14-PadP$15)") (class "Default")
      (node (ref "CMP8") (pin "P$15") (pinfunction "OUT_14_P$15") (pintype "output"))
    )
    (net (code "182") (name "unconnected-(CMP8-OUT_15-PadP$16)") (class "Default")
      (node (ref "CMP8") (pin "P$16") (pinfunction "OUT_15_P$16") (pintype "output"))
    )
    (net (code "183") (name "unconnected-(CMP8-PadINPUT)") (class "Default")
      (node (ref "CMP8") (pin "INPUT") (pinfunction "INPUT_INPUT") (pintype "input"))
    )
    (net (code "184") (name "unconnected-(CMP11-N-PadOUT_M)") (class "Default")
      (node (ref "CMP11") (pin "OUT_M") (pinfunction "N_OUT_M") (pintype "output"))
    )
    (net (code "185") (name "unconnected-(CMP12-OUT_15-PadP$16)") (class "Default")
      (node (ref "CMP12") (pin "P$16") (pinfunction "OUT_15_P$16") (pintype "output"))
    )
    (net (code "186") (name "unconnected-(CMP13-N-PadOUT_M)") (class "Default")
      (node (ref "CMP13") (pin "OUT_M") (pinfunction "N_OUT_M") (pintype "output"))
    )
    (net (code "187") (name "unconnected-(CMP15-IN_10-PadP$11)") (class "Default")
      (node (ref "CMP15") (pin "P$11") (pinfunction "IN_10_P$11") (pintype "input"))
    )
    (net (code "188") (name "unconnected-(CMP15-IN_11-PadP$12)") (class "Default")
      (node (ref "CMP15") (pin "P$12") (pinfunction "IN_11_P$12") (pintype "input"))
    )
    (net (code "189") (name "unconnected-(CMP15-IN_12-PadP$13)") (class "Default")
      (node (ref "CMP15") (pin "P$13") (pinfunction "IN_12_P$13") (pintype "input"))
    )
    (net (code "190") (name "unconnected-(CMP15-IN_13-PadP$14)") (class "Default")
      (node (ref "CMP15") (pin "P$14") (pinfunction "IN_13_P$14") (pintype "input"))
    )
    (net (code "191") (name "unconnected-(CMP15-IN_14-PadP$15)") (class "Default")
      (node (ref "CMP15") (pin "P$15") (pinfunction "IN_14_P$15") (pintype "input"))
    )
    (net (code "192") (name "unconnected-(CMP15-IN_15-PadP$16)") (class "Default")
      (node (ref "CMP15") (pin "P$16") (pinfunction "IN_15_P$16") (pintype "input"))
    )
    (net (code "193") (name "unconnected-(CMP15-OUT-PadINPUT)") (class "Default")
      (node (ref "CMP15") (pin "INPUT") (pinfunction "OUT_INPUT") (pintype "output"))
    )
    (net (code "194") (name "unconnected-(CMP17-N-PadOUT_M)") (class "Default")
      (node (ref "CMP17") (pin "OUT_M") (pinfunction "N_OUT_M") (pintype "output"))
    )
    (net (code "195") (name "unconnected-(CMP18-P-PadOUT_P)") (class "Default")
      (node (ref "CMP18") (pin "OUT_P") (pinfunction "P_OUT_P") (pintype "output"))
    )
    (net (code "196") (name "unconnected-(CMP28-IN_15-PadP$16)") (class "Default")
      (node (ref "CMP28") (pin "P$16") (pinfunction "IN_15_P$16") (pintype "input"))
    )
    (net (code "197") (name "unconnected-(CMP31-N-PadOUT_M)") (class "Default")
      (node (ref "CMP31") (pin "OUT_M") (pinfunction "N_OUT_M") (pintype "output"))
    )
    (net (code "198") (name "unconnected-(CMP32-N-PadOUT_M)") (class "Default")
      (node (ref "CMP32") (pin "OUT_M") (pinfunction "N_OUT_M") (pintype "output"))
    )
    (net (code "199") (name "unconnected-(CMP33-N-PadOUT_M)") (class "Default")
      (node (ref "CMP33") (pin "OUT_M") (pinfunction "N_OUT_M") (pintype "output"))
    )
    (net (code "200") (name "unconnected-(CMP34-N-PadOUT_M)") (class "Default")
      (node (ref "CMP34") (pin "OUT_M") (pinfunction "N_OUT_M") (pintype "output"))
    )
    (net (code "201") (name "unconnected-(CMP38-P-PadOUT_P)") (class "Default")
      (node (ref "CMP38") (pin "OUT_P") (pinfunction "P_OUT_P") (pintype "output"))
    )
    (net (code "202") (name "unconnected-(CMP39-N-PadOUT_M)") (class "Default")
      (node (ref "CMP39") (pin "OUT_M") (pinfunction "N_OUT_M") (pintype "output"))
    )
    (net (code "203") (name "unconnected-(CMP43-N-PadOUT_M)") (class "Default")
      (node (ref "CMP43") (pin "OUT_M") (pinfunction "N_OUT_M") (pintype "output"))
    )
    (net (code "204") (name "unconnected-(CMP47-M-PadOUT_M)") (class "Default")
      (node (ref "CMP47") (pin "OUT_M") (pinfunction "M_OUT_M") (pintype "output"))
    )
    (net (code "205") (name "unconnected-(CMP49-N-PadOUT_M)") (class "Default")
      (node (ref "CMP49") (pin "OUT_M") (pinfunction "N_OUT_M") (pintype "output"))
    )
    (net (code "206") (name "unconnected-(CMP50-N-PadOUT_M)") (class "Default")
      (node (ref "CMP50") (pin "OUT_M") (pinfunction "N_OUT_M") (pintype "output"))
    )
    (net (code "207") (name "unconnected-(CMP51-P-PadOUT_P)") (class "Default")
      (node (ref "CMP51") (pin "OUT_P") (pinfunction "P_OUT_P") (pintype "output"))
    )
    (net (code "208") (name "unconnected-(CMP52-N-PadOUT_M)") (class "Default")
      (node (ref "CMP52") (pin "OUT_M") (pinfunction "N_OUT_M") (pintype "output"))
    )
    (net (code "209") (name "unconnected-(CMP53-PadP)") (class "Default")
      (node (ref "CMP53") (pin "P") (pinfunction "P_P") (pintype "output"))
    )
    (net (code "210") (name "unconnected-(CMP56-P-PadOUT_P)") (class "Default")
      (node (ref "CMP56") (pin "OUT_P") (pinfunction "P_OUT_P") (pintype "output"))
    )
    (net (code "211") (name "unconnected-(CMP57-N-PadOUT_M)") (class "Default")
      (node (ref "CMP57") (pin "OUT_M") (pinfunction "N_OUT_M") (pintype "output"))
    )
    (net (code "212") (name "unconnected-(CMP59-N-PadOUT_M)") (class "Default")
      (node (ref "CMP59") (pin "OUT_M") (pinfunction "N_OUT_M") (pintype "output"))
    )
    (net (code "213") (name "unconnected-(CMP61-N-PadOUT_M)") (class "Default")
      (node (ref "CMP61") (pin "OUT_M") (pinfunction "N_OUT_M") (pintype "output"))
    )
    (net (code "214") (name "unconnected-(CMP63-P-PadOUT_P)") (class "Default")
      (node (ref "CMP63") (pin "OUT_P") (pinfunction "P_OUT_P") (pintype "output"))
    )
    (net (code "215") (name "unconnected-(CMP64-N-PadOUT_M)") (class "Default")
      (node (ref "CMP64") (pin "OUT_M") (pinfunction "N_OUT_M") (pintype "output"))
    )
    (net (code "216") (name "unconnected-(CMP65-N-PadOUT_M)") (class "Default")
      (node (ref "CMP65") (pin "OUT_M") (pinfunction "N_OUT_M") (pintype "output"))
    )
    (net (code "217") (name "unconnected-(CMP66-P-PadOUT_P)") (class "Default")
      (node (ref "CMP66") (pin "OUT_P") (pinfunction "P_OUT_P") (pintype "output"))
    )
    (net (code "218") (name "unconnected-(CMP67-N-PadOUT_M)") (class "Default")
      (node (ref "CMP67") (pin "OUT_M") (pinfunction "N_OUT_M") (pintype "output"))
    )
    (net (code "219") (name "unconnected-(CMP68-N-PadOUT_M)") (class "Default")
      (node (ref "CMP68") (pin "OUT_M") (pinfunction "N_OUT_M") (pintype "output"))
    )
    (net (code "220") (name "unconnected-(CMP69-N-PadOUT_M)") (class "Default")
      (node (ref "CMP69") (pin "OUT_M") (pinfunction "N_OUT_M") (pintype "output"))
    )
    (net (code "221") (name "unconnected-(CMP70-N-PadOUT_M)") (class "Default")
      (node (ref "CMP70") (pin "OUT_M") (pinfunction "N_OUT_M") (pintype "output"))
    )
    (net (code "222") (name "unconnected-(CMP71-P-PadOUT_P)") (class "Default")
      (node (ref "CMP71") (pin "OUT_P") (pinfunction "P_OUT_P") (pintype "output"))
    )
    (net (code "223") (name "unconnected-(CMP72-N-PadOUT_M)") (class "Default")
      (node (ref "CMP72") (pin "OUT_M") (pinfunction "N_OUT_M") (pintype "output"))
    )
    (net (code "224") (name "unconnected-(CMP73-P-PadOUT_P)") (class "Default")
      (node (ref "CMP73") (pin "OUT_P") (pinfunction "P_OUT_P") (pintype "output"))
    )
    (net (code "225") (name "unconnected-(CMP74-N-PadOUT_M)") (class "Default")
      (node (ref "CMP74") (pin "OUT_M") (pinfunction "N_OUT_M") (pintype "output"))
    )
    (net (code "226") (name "unconnected-(CMP80-OUT_12-PadP$13)") (class "Default")
      (node (ref "CMP80") (pin "P$13") (pinfunction "OUT_12_P$13") (pintype "output"))
    )
    (net (code "227") (name "unconnected-(CMP80-OUT_13-PadP$14)") (class "Default")
      (node (ref "CMP80") (pin "P$14") (pinfunction "OUT_13_P$14") (pintype "output"))
    )
    (net (code "228") (name "unconnected-(CMP80-OUT_14-PadP$15)") (class "Default")
      (node (ref "CMP80") (pin "P$15") (pinfunction "OUT_14_P$15") (pintype "output"))
    )
    (net (code "229") (name "unconnected-(CMP80-OUT_15-PadP$16)") (class "Default")
      (node (ref "CMP80") (pin "P$16") (pinfunction "OUT_15_P$16") (pintype "output"))
    )
  )
)
